# ppc_ddr2.net
KiCad netlist of a schematic drawn in Altium Designer
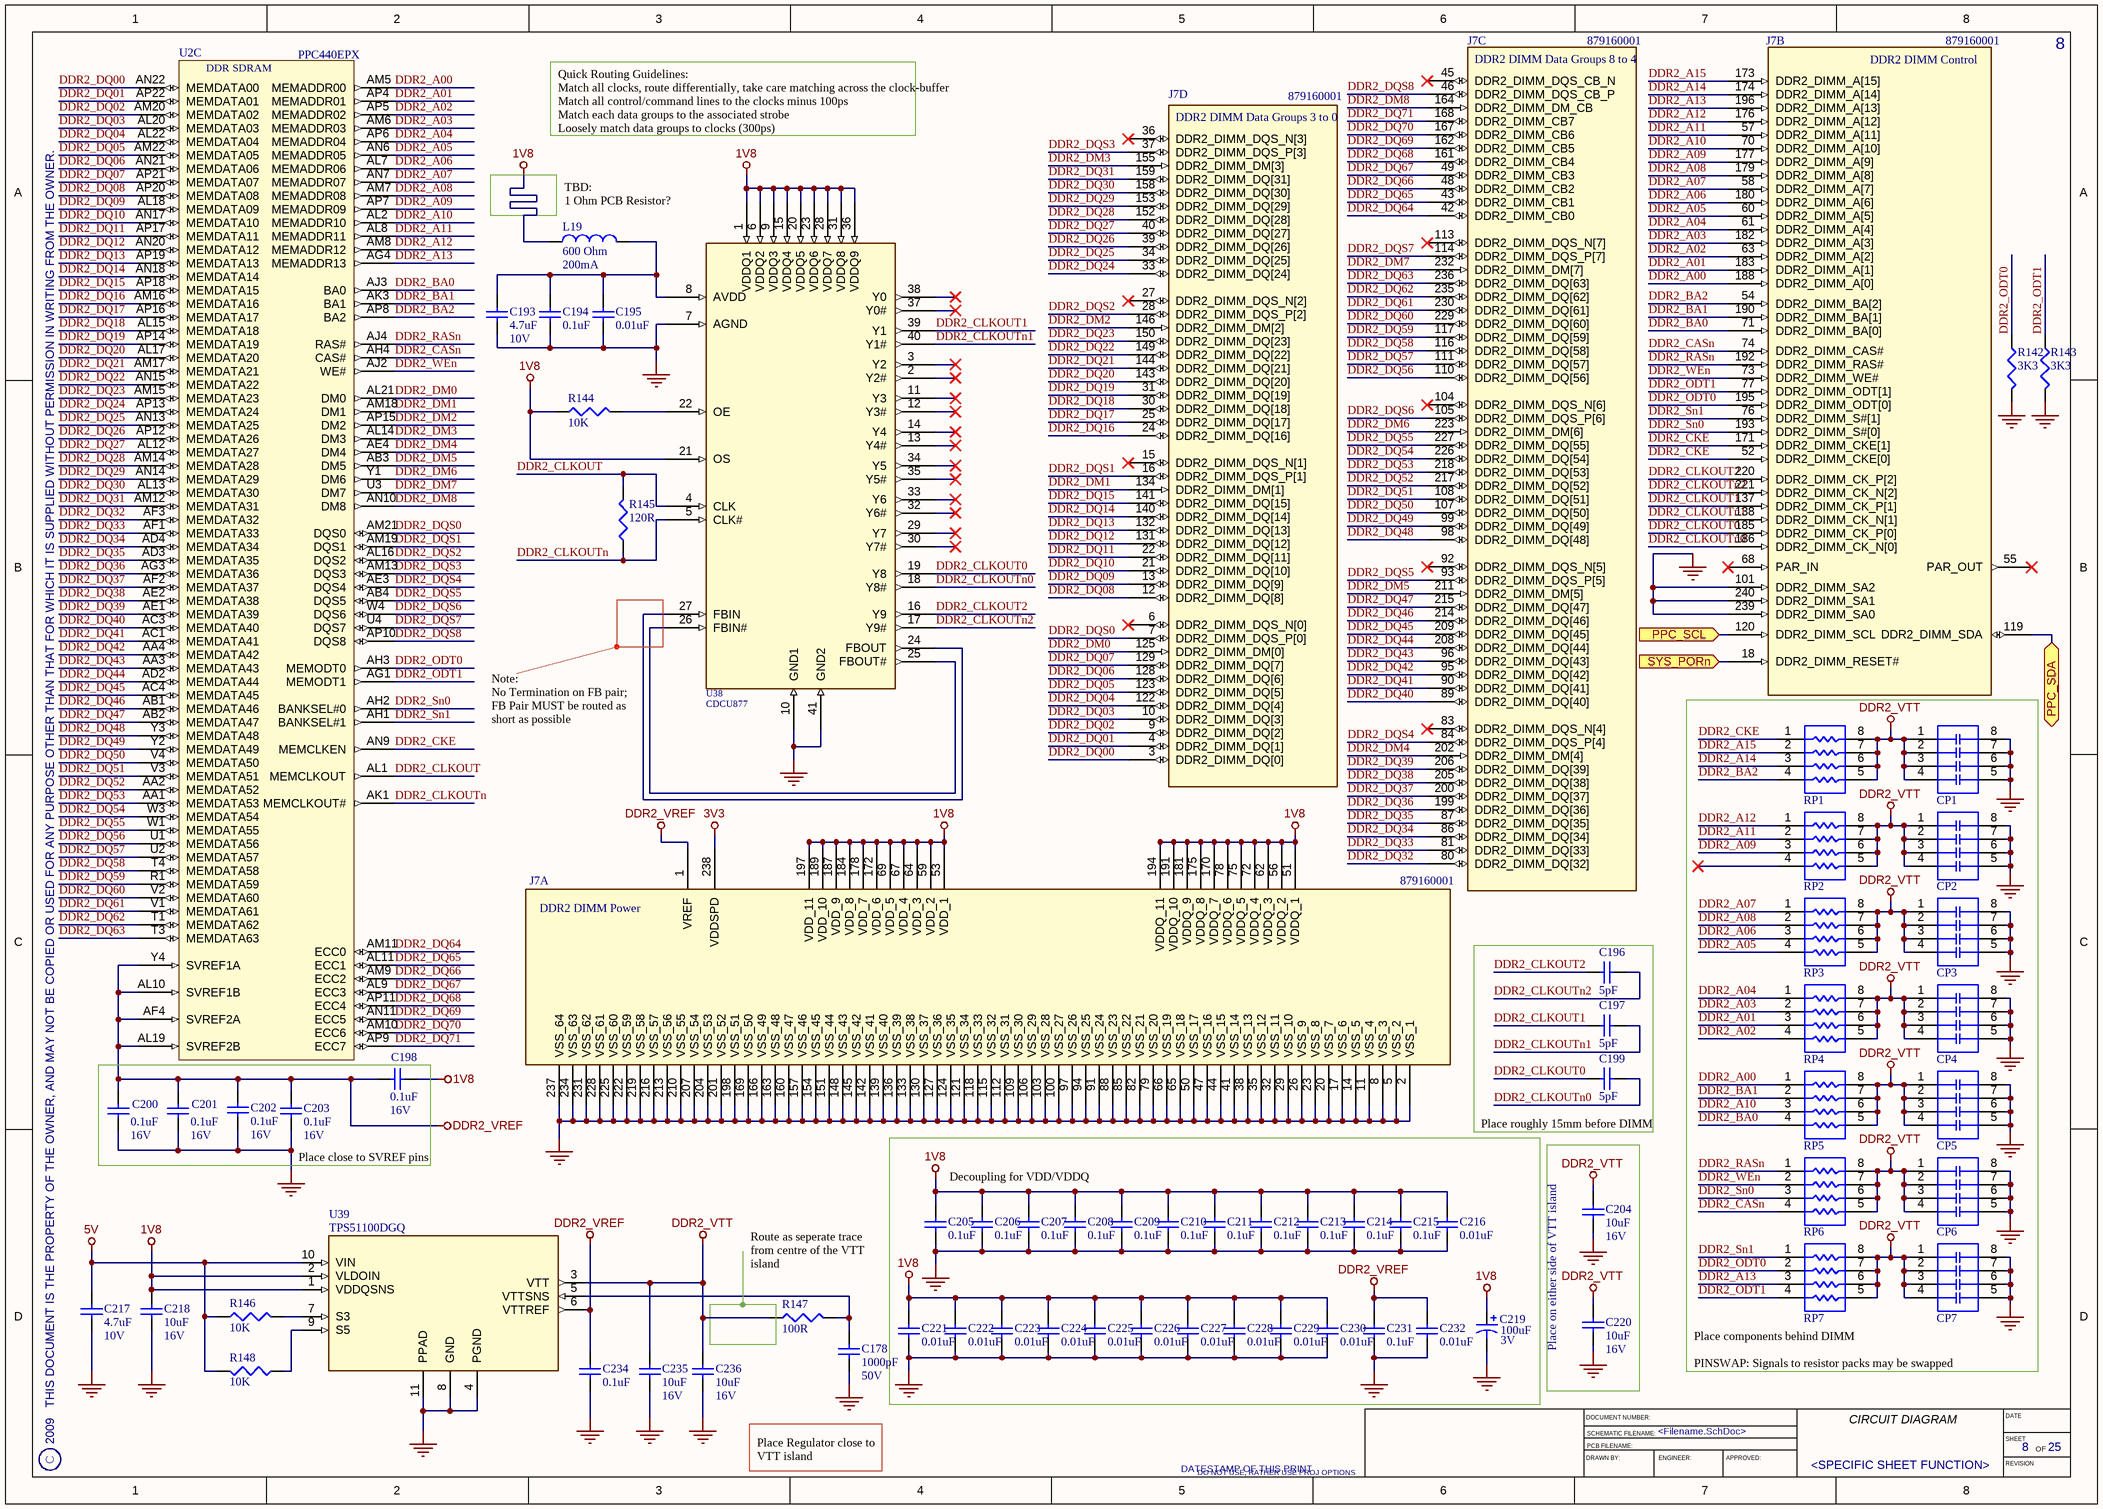
[diagram p0: ppc_ddr2.SchDoc]

(export (version "E")
  (design (tool "Eeschema 10.0.6"))
  (components
    (comp (ref "C178")
      (value "1000pF")
      (footprint "CAPC1005L")
      (description "Capacitor")
      (fields
        (field (name "MANUFACTURER") "Murata")
        (field (name "PART") "GRM155R61A102KA01B")
        (field (name "RATING") "50V")
      )
      (libsource (lib "SKA-MeerKAT_PASSIVE") (part "CapStd"))
    )
    (comp (ref "C193")
      (value "4.7uF")
      (footprint "2012-0805_CAPC2012X11N")
      (description "Capacitor")
      (fields
        (field (name "MANUFACTURER") "MURATA")
        (field (name "PART") "GRM21BR61E475KA12K")
        (field (name "RATING") "10V")
      )
      (libsource (lib "SKA-MeerKAT_PASSIVE") (part "CapStd"))
    )
    (comp (ref "C194")
      (value "0.1uF")
      (footprint "CAPC1005L")
      (description "Capacitor")
      (fields (field (name "MANUFACTURER") "MURATA") (field (name "PART") "GRM155R71A104KA01B"))
      (libsource (lib "SKA-MeerKAT_PASSIVE") (part "CapStd"))
    )
    (comp (ref "C195")
      (value "0.01uF")
      (footprint "CAPC1005L")
      (description "Capacitor")
      (fields (field (name "MANUFACTURER") "MURATA") (field (name "PART") "GRM155R7EA103KA01B"))
      (libsource (lib "SKA-MeerKAT_PASSIVE") (part "CapStd"))
    )
    (comp (ref "C196")
      (value "5pF")
      (footprint "CAPC1005L")
      (description "Capacitor")
      (fields (field (name "MANUFACTURER") "MURATA") (field (name "PART") "GRM1555C1H5R0CZ01B"))
      (libsource (lib "SKA-MeerKAT_PASSIVE") (part "CapStd"))
    )
    (comp (ref "C197")
      (value "5pF")
      (footprint "CAPC1005L")
      (description "Capacitor")
      (fields (field (name "MANUFACTURER") "MURATA") (field (name "PART") "GRM1555C1H5R0CZ01B"))
      (libsource (lib "SKA-MeerKAT_PASSIVE") (part "CapStd"))
    )
    (comp (ref "C198")
      (value "0.1uF")
      (footprint "CAPC1005L")
      (description "Capacitor")
      (fields
        (field (name "MANUFACTURER") "VENKEL")
        (field (name "PART") "C0402X7R160-104KN")
        (field (name "RATING") "16V")
      )
      (libsource (lib "SKA-MeerKAT_PASSIVE") (part "CapStd"))
    )
    (comp (ref "C199")
      (value "5pF")
      (footprint "CAPC1005L")
      (description "Capacitor")
      (fields (field (name "MANUFACTURER") "MURATA") (field (name "PART") "GRM1555C1H5R0CZ01B"))
      (libsource (lib "SKA-MeerKAT_PASSIVE") (part "CapStd"))
    )
    (comp (ref "C200")
      (value "0.1uF")
      (footprint "CAPC1005L")
      (description "Capacitor")
      (fields
        (field (name "MANUFACTURER") "VENKEL")
        (field (name "PART") "C0402X7R160-104KN")
        (field (name "RATING") "16V")
      )
      (libsource (lib "SKA-MeerKAT_PASSIVE") (part "CapStd"))
    )
    (comp (ref "C201")
      (value "0.1uF")
      (footprint "CAPC1005L")
      (description "Capacitor")
      (fields
        (field (name "MANUFACTURER") "VENKEL")
        (field (name "PART") "C0402X7R160-104KN")
        (field (name "RATING") "16V")
      )
      (libsource (lib "SKA-MeerKAT_PASSIVE") (part "CapStd"))
    )
    (comp (ref "C202")
      (value "0.1uF")
      (footprint "CAPC1005L")
      (description "Capacitor")
      (fields
        (field (name "MANUFACTURER") "VENKEL")
        (field (name "PART") "C0402X7R160-104KN")
        (field (name "RATING") "16V")
      )
      (libsource (lib "SKA-MeerKAT_PASSIVE") (part "CapStd"))
    )
    (comp (ref "C203")
      (value "0.1uF")
      (footprint "CAPC1005L")
      (description "Capacitor")
      (fields
        (field (name "MANUFACTURER") "VENKEL")
        (field (name "PART") "C0402X7R160-104KN")
        (field (name "RATING") "16V")
      )
      (libsource (lib "SKA-MeerKAT_PASSIVE") (part "CapStd"))
    )
    (comp (ref "C204")
      (value "10uF")
      (footprint "CAPC3225L")
      (description "Capacitor")
      (fields
        (field (name "MANUFACTURER") "MURATA")
        (field (name "PART") "GRM32DR61C106KA01K")
        (field (name "RATING") "16V")
      )
      (libsource (lib "SKA-MeerKAT_PASSIVE") (part "CapStd"))
    )
    (comp (ref "C205")
      (value "0.1uF")
      (footprint "CAPC1005L")
      (description "Capacitor")
      (fields (field (name "MANUFACTURER") "MURATA") (field (name "PART") "GRM155R71A104KA01B"))
      (libsource (lib "SKA-MeerKAT_PASSIVE") (part "CapStd"))
    )
    (comp (ref "C206")
      (value "0.1uF")
      (footprint "CAPC1005L")
      (description "Capacitor")
      (fields (field (name "MANUFACTURER") "MURATA") (field (name "PART") "GRM155R71A104KA01B"))
      (libsource (lib "SKA-MeerKAT_PASSIVE") (part "CapStd"))
    )
    (comp (ref "C207")
      (value "0.1uF")
      (footprint "CAPC1005L")
      (description "Capacitor")
      (fields (field (name "MANUFACTURER") "MURATA") (field (name "PART") "GRM155R71A104KA01B"))
      (libsource (lib "SKA-MeerKAT_PASSIVE") (part "CapStd"))
    )
    (comp (ref "C208")
      (value "0.1uF")
      (footprint "CAPC1005L")
      (description "Capacitor")
      (fields (field (name "MANUFACTURER") "MURATA") (field (name "PART") "GRM155R71A104KA01B"))
      (libsource (lib "SKA-MeerKAT_PASSIVE") (part "CapStd"))
    )
    (comp (ref "C209")
      (value "0.1uF")
      (footprint "CAPC1005L")
      (description "Capacitor")
      (fields (field (name "MANUFACTURER") "MURATA") (field (name "PART") "GRM155R71A104KA01B"))
      (libsource (lib "SKA-MeerKAT_PASSIVE") (part "CapStd"))
    )
    (comp (ref "C210")
      (value "0.1uF")
      (footprint "CAPC1005L")
      (description "Capacitor")
      (fields (field (name "MANUFACTURER") "MURATA") (field (name "PART") "GRM155R71A104KA01B"))
      (libsource (lib "SKA-MeerKAT_PASSIVE") (part "CapStd"))
    )
    (comp (ref "C211")
      (value "0.1uF")
      (footprint "CAPC1005L")
      (description "Capacitor")
      (fields (field (name "MANUFACTURER") "MURATA") (field (name "PART") "GRM155R71A104KA01B"))
      (libsource (lib "SKA-MeerKAT_PASSIVE") (part "CapStd"))
    )
    (comp (ref "C212")
      (value "0.1uF")
      (footprint "CAPC1005L")
      (description "Capacitor")
      (fields (field (name "MANUFACTURER") "MURATA") (field (name "PART") "GRM155R71A104KA01B"))
      (libsource (lib "SKA-MeerKAT_PASSIVE") (part "CapStd"))
    )
    (comp (ref "C213")
      (value "0.1uF")
      (footprint "CAPC1005L")
      (description "Capacitor")
      (fields (field (name "MANUFACTURER") "MURATA") (field (name "PART") "GRM155R71A104KA01B"))
      (libsource (lib "SKA-MeerKAT_PASSIVE") (part "CapStd"))
    )
    (comp (ref "C214")
      (value "0.1uF")
      (footprint "CAPC1005L")
      (description "Capacitor")
      (fields (field (name "MANUFACTURER") "MURATA") (field (name "PART") "GRM155R71A104KA01B"))
      (libsource (lib "SKA-MeerKAT_PASSIVE") (part "CapStd"))
    )
    (comp (ref "C215")
      (value "0.1uF")
      (footprint "CAPC1005L")
      (description "Capacitor")
      (fields (field (name "MANUFACTURER") "MURATA") (field (name "PART") "GRM155R71A104KA01B"))
      (libsource (lib "SKA-MeerKAT_PASSIVE") (part "CapStd"))
    )
    (comp (ref "C216")
      (value "0.01uF")
      (footprint "CAPC1005L")
      (description "Capacitor")
      (fields (field (name "MANUFACTURER") "MURATA") (field (name "PART") "GRM155R7EA103KA01B"))
      (libsource (lib "SKA-MeerKAT_PASSIVE") (part "CapStd"))
    )
    (comp (ref "C217")
      (value "4.7uF")
      (footprint "2012-0805_CAPC2012X11N")
      (description "Capacitor")
      (fields
        (field (name "MANUFACTURER") "MURATA")
        (field (name "PART") "GRM21BR61E475KA12K")
        (field (name "RATING") "10V")
      )
      (libsource (lib "SKA-MeerKAT_PASSIVE") (part "CapStd"))
    )
    (comp (ref "C218")
      (value "10uF")
      (footprint "CAPC3225L")
      (description "Capacitor")
      (fields
        (field (name "MANUFACTURER") "MURATA")
        (field (name "PART") "GRM32DR61C106KA01K")
        (field (name "RATING") "16V")
      )
      (libsource (lib "SKA-MeerKAT_PASSIVE") (part "CapStd"))
    )
    (comp (ref "C219")
      (value "100uF")
      (footprint "Tantalum-7343-CASE-D_CAPM7343X31N")
      (description "Polarized Capacitor")
      (fields
        (field (name "RATING") "3V")
        (field (name "MANUFACTURER") "AVX")
        (field (name "PART") "TPSB107K006R")
      )
      (libsource (lib "SKA-MeerKAT_PASSIVE") (part "CapPol"))
    )
    (comp (ref "C220")
      (value "10uF")
      (footprint "CAPC3225L")
      (description "Capacitor")
      (fields
        (field (name "MANUFACTURER") "MURATA")
        (field (name "PART") "GRM32DR61C106KA01K")
        (field (name "RATING") "16V")
      )
      (libsource (lib "SKA-MeerKAT_PASSIVE") (part "CapStd"))
    )
    (comp (ref "C221")
      (value "0.01uF")
      (footprint "CAPC1005L")
      (description "Capacitor")
      (fields (field (name "MANUFACTURER") "MURATA") (field (name "PART") "GRM155R7EA103KA01B"))
      (libsource (lib "SKA-MeerKAT_PASSIVE") (part "CapStd"))
    )
    (comp (ref "C222")
      (value "0.01uF")
      (footprint "CAPC1005L")
      (description "Capacitor")
      (fields (field (name "MANUFACTURER") "MURATA") (field (name "PART") "GRM155R7EA103KA01B"))
      (libsource (lib "SKA-MeerKAT_PASSIVE") (part "CapStd"))
    )
    (comp (ref "C223")
      (value "0.01uF")
      (footprint "CAPC1005L")
      (description "Capacitor")
      (fields (field (name "MANUFACTURER") "MURATA") (field (name "PART") "GRM155R7EA103KA01B"))
      (libsource (lib "SKA-MeerKAT_PASSIVE") (part "CapStd"))
    )
    (comp (ref "C224")
      (value "0.01uF")
      (footprint "CAPC1005L")
      (description "Capacitor")
      (fields (field (name "MANUFACTURER") "MURATA") (field (name "PART") "GRM155R7EA103KA01B"))
      (libsource (lib "SKA-MeerKAT_PASSIVE") (part "CapStd"))
    )
    (comp (ref "C225")
      (value "0.01uF")
      (footprint "CAPC1005L")
      (description "Capacitor")
      (fields (field (name "MANUFACTURER") "MURATA") (field (name "PART") "GRM155R7EA103KA01B"))
      (libsource (lib "SKA-MeerKAT_PASSIVE") (part "CapStd"))
    )
    (comp (ref "C226")
      (value "0.01uF")
      (footprint "CAPC1005L")
      (description "Capacitor")
      (fields (field (name "MANUFACTURER") "MURATA") (field (name "PART") "GRM155R7EA103KA01B"))
      (libsource (lib "SKA-MeerKAT_PASSIVE") (part "CapStd"))
    )
    (comp (ref "C227")
      (value "0.01uF")
      (footprint "CAPC1005L")
      (description "Capacitor")
      (fields (field (name "MANUFACTURER") "MURATA") (field (name "PART") "GRM155R7EA103KA01B"))
      (libsource (lib "SKA-MeerKAT_PASSIVE") (part "CapStd"))
    )
    (comp (ref "C228")
      (value "0.01uF")
      (footprint "CAPC1005L")
      (description "Capacitor")
      (fields (field (name "MANUFACTURER") "MURATA") (field (name "PART") "GRM155R7EA103KA01B"))
      (libsource (lib "SKA-MeerKAT_PASSIVE") (part "CapStd"))
    )
    (comp (ref "C229")
      (value "0.01uF")
      (footprint "CAPC1005L")
      (description "Capacitor")
      (fields (field (name "MANUFACTURER") "MURATA") (field (name "PART") "GRM155R7EA103KA01B"))
      (libsource (lib "SKA-MeerKAT_PASSIVE") (part "CapStd"))
    )
    (comp (ref "C230")
      (value "0.01uF")
      (footprint "CAPC1005L")
      (description "Capacitor")
      (fields (field (name "MANUFACTURER") "MURATA") (field (name "PART") "GRM155R7EA103KA01B"))
      (libsource (lib "SKA-MeerKAT_PASSIVE") (part "CapStd"))
    )
    (comp (ref "C231")
      (value "0.1uF")
      (footprint "CAPC1005L")
      (description "Capacitor")
      (fields (field (name "MANUFACTURER") "MURATA") (field (name "PART") "GRM155R71A104KA01B"))
      (libsource (lib "SKA-MeerKAT_PASSIVE") (part "CapStd"))
    )
    (comp (ref "C232")
      (value "0.01uF")
      (footprint "CAPC1005L")
      (description "Capacitor")
      (fields (field (name "MANUFACTURER") "MURATA") (field (name "PART") "GRM155R7EA103KA01B"))
      (libsource (lib "SKA-MeerKAT_PASSIVE") (part "CapStd"))
    )
    (comp (ref "C234")
      (value "0.1uF")
      (footprint "CAPC1005L")
      (description "Capacitor")
      (fields (field (name "MANUFACTURER") "MURATA") (field (name "PART") "GRM155R71A104KA01B"))
      (libsource (lib "SKA-MeerKAT_PASSIVE") (part "CapStd"))
    )
    (comp (ref "C235")
      (value "10uF")
      (footprint "CAPC3225L")
      (description "Capacitor")
      (fields
        (field (name "MANUFACTURER") "MURATA")
        (field (name "PART") "GRM32DR61C106KA01K")
        (field (name "RATING") "16V")
      )
      (libsource (lib "SKA-MeerKAT_PASSIVE") (part "CapStd"))
    )
    (comp (ref "C236")
      (value "10uF")
      (footprint "CAPC3225L")
      (description "Capacitor")
      (fields
        (field (name "MANUFACTURER") "MURATA")
        (field (name "PART") "GRM32DR61C106KA01K")
        (field (name "RATING") "16V")
      )
      (libsource (lib "SKA-MeerKAT_PASSIVE") (part "CapStd"))
    )
    (comp (ref "CP1")
      (value "CapPack4")
      (footprint "CAPCAF50P125X200X100-8N")
      (description "Isolated Capacitor Network")
      (fields (field (name "PART") "GNM214B11C104MA01B") (field (name "MANUFACTURER") "MURATA"))
      (libsource (lib "SKA-MeerKAT_PASSIVE") (part "CapPack4"))
    )
    (comp (ref "CP2")
      (value "CapPack4")
      (footprint "CAPCAF50P125X200X100-8N")
      (description "Isolated Capacitor Network")
      (fields (field (name "PART") "GNM214B11C104MA01B") (field (name "MANUFACTURER") "MURATA"))
      (libsource (lib "SKA-MeerKAT_PASSIVE") (part "CapPack4"))
    )
    (comp (ref "CP3")
      (value "CapPack4")
      (footprint "CAPCAF50P125X200X100-8N")
      (description "Isolated Capacitor Network")
      (fields (field (name "PART") "GNM214B11C104MA01B") (field (name "MANUFACTURER") "MURATA"))
      (libsource (lib "SKA-MeerKAT_PASSIVE") (part "CapPack4"))
    )
    (comp (ref "CP4")
      (value "CapPack4")
      (footprint "CAPCAF50P125X200X100-8N")
      (description "Isolated Capacitor Network")
      (fields (field (name "PART") "GNM214B11C104MA01B") (field (name "MANUFACTURER") "MURATA"))
      (libsource (lib "SKA-MeerKAT_PASSIVE") (part "CapPack4"))
    )
    (comp (ref "CP5")
      (value "CapPack4")
      (footprint "CAPCAF50P125X200X100-8N")
      (description "Isolated Capacitor Network")
      (fields (field (name "PART") "GNM214B11C104MA01B") (field (name "MANUFACTURER") "MURATA"))
      (libsource (lib "SKA-MeerKAT_PASSIVE") (part "CapPack4"))
    )
    (comp (ref "CP6")
      (value "CapPack4")
      (footprint "CAPCAF50P125X200X100-8N")
      (description "Isolated Capacitor Network")
      (fields (field (name "PART") "GNM214B11C104MA01B") (field (name "MANUFACTURER") "MURATA"))
      (libsource (lib "SKA-MeerKAT_PASSIVE") (part "CapPack4"))
    )
    (comp (ref "CP7")
      (value "CapPack4")
      (footprint "CAPCAF50P125X200X100-8N")
      (description "Isolated Capacitor Network")
      (fields (field (name "PART") "GNM214B11C104MA01B") (field (name "MANUFACTURER") "MURATA"))
      (libsource (lib "SKA-MeerKAT_PASSIVE") (part "CapPack4"))
    )
    (comp (ref "J7")
      (value "879160001")
      (footprint "MOLEX87916001")
      (description "240-pin DDR2 DIMM Socket")
      (fields (field (name "MANUFACTURER") "MOLEX"))
      (libsource (lib "SKA-MeerKAT_CONNECTOR") (part "ddr2_dimm_240"))
    )
    (comp (ref "L19")
      (value "600 Ohm")
      (footprint "INDC2012L")
      (description "Inductor")
      (fields
        (field (name "MANUFACTURER") "Murata")
        (field (name "PART") "BLM21B601SPT")
        (field (name "RATING") "200mA")
      )
      (libsource (lib "SKA-MeerKAT_PASSIVE") (part "Inductor"))
    )
    (comp (ref "R142")
      (value "3K3")
      (footprint "RESC1608L")
      (description "Resistor")
      (fields (field (name "PART") "0402WGJ033T1E") (field (name "MANUFACTURER") "ROYALOHM"))
      (libsource (lib "SKA-MeerKAT_PASSIVE") (part "ResStd"))
    )
    (comp (ref "R143")
      (value "3K3")
      (footprint "RESC1608L")
      (description "Resistor")
      (fields (field (name "PART") "0402WGJ033T1E") (field (name "MANUFACTURER") "ROYALOHM"))
      (libsource (lib "SKA-MeerKAT_PASSIVE") (part "ResStd"))
    )
    (comp (ref "R144")
      (value "10K")
      (footprint "RESC1608L")
      (description "Resistor")
      (fields (field (name "PART") "0402WGJ103T1E") (field (name "MANUFACTURER") "ROYALOHM"))
      (libsource (lib "SKA-MeerKAT_PASSIVE") (part "ResStd"))
    )
    (comp (ref "R145")
      (value "120R")
      (footprint "RESC1005L")
      (description "Resistor")
      (fields (field (name "PART") "0402WGJ0120T1E") (field (name "MANUFACTURER") "ROYALOHM"))
      (libsource (lib "SKA-MeerKAT_PASSIVE") (part "ResStd"))
    )
    (comp (ref "R146")
      (value "10K")
      (footprint "RESC1005L")
      (description "Resistor")
      (fields (field (name "PART") "0402WGJ103T1E") (field (name "MANUFACTURER") "ROYALOHM"))
      (libsource (lib "SKA-MeerKAT_PASSIVE") (part "ResStd"))
    )
    (comp (ref "R147")
      (value "100R")
      (footprint "RESC1005L")
      (description "Resistor")
      (fields (field (name "PART") "0402WGJ0101T1E") (field (name "MANUFACTURER") "ROYALOHM"))
      (libsource (lib "SKA-MeerKAT_PASSIVE") (part "ResStd"))
    )
    (comp (ref "R148")
      (value "10K")
      (footprint "RESC1005L")
      (description "Resistor")
      (fields (field (name "PART") "0402WGJ103T1E") (field (name "MANUFACTURER") "ROYALOHM"))
      (libsource (lib "SKA-MeerKAT_PASSIVE") (part "ResStd"))
    )
    (comp (ref "RP1")
      (value "ResPack4")
      (footprint "RESCAV50P100X200X55-8N")
      (description "Isolated Resistor Network")
      (fields (field (name "PART") "4D02WGJ0510B1E") (field (name "MANUFACTURER") "ROYAL OHM"))
      (libsource (lib "SKA-MeerKAT_PASSIVE") (part "ResPack4"))
    )
    (comp (ref "RP2")
      (value "ResPack4")
      (footprint "RESCAV50P100X200X55-8N")
      (description "Isolated Resistor Network")
      (fields (field (name "PART") "4D02WGJ0510B1E") (field (name "MANUFACTURER") "ROYAL OHM"))
      (libsource (lib "SKA-MeerKAT_PASSIVE") (part "ResPack4"))
    )
    (comp (ref "RP3")
      (value "ResPack4")
      (footprint "RESCAV50P100X200X55-8N")
      (description "Isolated Resistor Network")
      (fields (field (name "PART") "4D02WGJ0510B1E") (field (name "MANUFACTURER") "ROYAL OHM"))
      (libsource (lib "SKA-MeerKAT_PASSIVE") (part "ResPack4"))
    )
    (comp (ref "RP4")
      (value "ResPack4")
      (footprint "RESCAV50P100X200X55-8N")
      (description "Isolated Resistor Network")
      (fields (field (name "PART") "4D02WGJ0510B1E") (field (name "MANUFACTURER") "ROYAL OHM"))
      (libsource (lib "SKA-MeerKAT_PASSIVE") (part "ResPack4"))
    )
    (comp (ref "RP5")
      (value "ResPack4")
      (footprint "RESCAV50P100X200X55-8N")
      (description "Isolated Resistor Network")
      (fields (field (name "PART") "4D02WGJ0510B1E") (field (name "MANUFACTURER") "ROYAL OHM"))
      (libsource (lib "SKA-MeerKAT_PASSIVE") (part "ResPack4"))
    )
    (comp (ref "RP6")
      (value "ResPack4")
      (footprint "RESCAV50P100X200X55-8N")
      (description "Isolated Resistor Network")
      (fields (field (name "PART") "4D02WGJ0510B1E") (field (name "MANUFACTURER") "ROYAL OHM"))
      (libsource (lib "SKA-MeerKAT_PASSIVE") (part "ResPack4"))
    )
    (comp (ref "RP7")
      (value "ResPack4")
      (footprint "RESCAV50P100X200X55-8N")
      (description "Isolated Resistor Network")
      (fields (field (name "PART") "4D02WGJ0510B1E") (field (name "MANUFACTURER") "ROYAL OHM"))
      (libsource (lib "SKA-MeerKAT_PASSIVE") (part "ResPack4"))
    )
    (comp (ref "U2")
      (value "PPC440EPX")
      (footprint "BGA680C100P34X34_3500X3500X265")
      (description "Applied Micro PPC440EPx")
      (fields (field (name "PART") "PPC440EPX-NTA533T") (field (name "MANUFACTURER") "AMCC"))
      (libsource (lib "SKA-MeerKAT_IC") (part "PPC440EPX"))
    )
    (comp (ref "U38")
      (value "CDCU877")
      (footprint "PQFN50P602X602X100-41N")
      (description "SSTL Zero-Delay Clock Buffer")
      (fields (field (name "MANUFACTURER") "Texas Instruments"))
      (libsource (lib "SKA-MeerKAT_IC") (part "CDCU877"))
    )
    (comp (ref "U39")
      (value "TPS51100DGQ")
      (footprint "SOP50P490X110-11N")
      (description "3A Sink/Source Regulator")
      (fields (field (name "MANUFACTURER") "Texas Instruments"))
      (libsource (lib "SKA-MeerKAT_IC") (part "TPS51100DGQ"))
    )
  )
  (nets
    (net (code "1") (name "/DDR2_A00") (class "Default")
      (node (ref "J7") (pin "188") (pinfunction "DDR2_DIMM_A[0]_188") (pintype "input"))
      (node (ref "RP5") (pin "1") (pinfunction "1_1") (pintype "passive"))
      (node (ref "U2") (pin "AM5") (pinfunction "MEMADDR00_AM5") (pintype "output"))
    )
    (net (code "2") (name "/DDR2_A01") (class "Default")
      (node (ref "J7") (pin "183") (pinfunction "DDR2_DIMM_A[1]_183") (pintype "input"))
      (node (ref "RP4") (pin "3") (pinfunction "3_3") (pintype "passive"))
      (node (ref "U2") (pin "AP4") (pinfunction "MEMADDR01_AP4") (pintype "output"))
    )
    (net (code "3") (name "/DDR2_A02") (class "Default")
      (node (ref "J7") (pin "63") (pinfunction "DDR2_DIMM_A[2]_63") (pintype "input"))
      (node (ref "RP4") (pin "4") (pinfunction "4_4") (pintype "passive"))
      (node (ref "U2") (pin "AP5") (pinfunction "MEMADDR02_AP5") (pintype "output"))
    )
    (net (code "4") (name "/DDR2_A03") (class "Default")
      (node (ref "J7") (pin "182") (pinfunction "DDR2_DIMM_A[3]_182") (pintype "input"))
      (node (ref "RP4") (pin "2") (pinfunction "2_2") (pintype "passive"))
      (node (ref "U2") (pin "AM6") (pinfunction "MEMADDR03_AM6") (pintype "output"))
    )
    (net (code "5") (name "/DDR2_A04") (class "Default")
      (node (ref "J7") (pin "61") (pinfunction "DDR2_DIMM_A[4]_61") (pintype "input"))
      (node (ref "RP4") (pin "1") (pinfunction "1_1") (pintype "passive"))
      (node (ref "U2") (pin "AP6") (pinfunction "MEMADDR04_AP6") (pintype "output"))
    )
    (net (code "6") (name "/DDR2_A05") (class "Default")
      (node (ref "J7") (pin "60") (pinfunction "DDR2_DIMM_A[5]_60") (pintype "input"))
      (node (ref "RP3") (pin "4") (pinfunction "4_4") (pintype "passive"))
      (node (ref "U2") (pin "AN6") (pinfunction "MEMADDR05_AN6") (pintype "output"))
    )
    (net (code "7") (name "/DDR2_A06") (class "Default")
      (node (ref "J7") (pin "180") (pinfunction "DDR2_DIMM_A[6]_180") (pintype "input"))
      (node (ref "RP3") (pin "3") (pinfunction "3_3") (pintype "passive"))
      (node (ref "U2") (pin "AL7") (pinfunction "MEMADDR06_AL7") (pintype "output"))
    )
    (net (code "8") (name "/DDR2_A07") (class "Default")
      (node (ref "J7") (pin "58") (pinfunction "DDR2_DIMM_A[7]_58") (pintype "input"))
      (node (ref "RP3") (pin "1") (pinfunction "1_1") (pintype "passive"))
      (node (ref "U2") (pin "AN7") (pinfunction "MEMADDR07_AN7") (pintype "output"))
    )
    (net (code "9") (name "/DDR2_A08") (class "Default")
      (node (ref "J7") (pin "179") (pinfunction "DDR2_DIMM_A[8]_179") (pintype "input"))
      (node (ref "RP3") (pin "2") (pinfunction "2_2") (pintype "passive"))
      (node (ref "U2") (pin "AM7") (pinfunction "MEMADDR08_AM7") (pintype "output"))
    )
    (net (code "10") (name "/DDR2_A09") (class "Default")
      (node (ref "J7") (pin "177") (pinfunction "DDR2_DIMM_A[9]_177") (pintype "input"))
      (node (ref "RP2") (pin "3") (pinfunction "3_3") (pintype "passive"))
      (node (ref "U2") (pin "AP7") (pinfunction "MEMADDR09_AP7") (pintype "output"))
    )
    (net (code "11") (name "/DDR2_A10") (class "Default")
      (node (ref "J7") (pin "70") (pinfunction "DDR2_DIMM_A[10]_70") (pintype "input"))
      (node (ref "RP5") (pin "3") (pinfunction "3_3") (pintype "passive"))
      (node (ref "U2") (pin "AL2") (pinfunction "MEMADDR10_AL2") (pintype "output"))
    )
    (net (code "12") (name "/DDR2_A11") (class "Default")
      (node (ref "J7") (pin "57") (pinfunction "DDR2_DIMM_A[11]_57") (pintype "input"))
      (node (ref "RP2") (pin "2") (pinfunction "2_2") (pintype "passive"))
      (node (ref "U2") (pin "AL8") (pinfunction "MEMADDR11_AL8") (pintype "output"))
    )
    (net (code "13") (name "/DDR2_A12") (class "Default")
      (node (ref "J7") (pin "176") (pinfunction "DDR2_DIMM_A[12]_176") (pintype "input"))
      (node (ref "RP2") (pin "1") (pinfunction "1_1") (pintype "passive"))
      (node (ref "U2") (pin "AM8") (pinfunction "MEMADDR12_AM8") (pintype "output"))
    )
    (net (code "14") (name "/DDR2_A13") (class "Default")
      (node (ref "J7") (pin "196") (pinfunction "DDR2_DIMM_A[13]_196") (pintype "input"))
      (node (ref "RP7") (pin "3") (pinfunction "3_3") (pintype "passive"))
      (node (ref "U2") (pin "AG4") (pinfunction "MEMADDR13_AG4") (pintype "output"))
    )
    (net (code "15") (name "/DDR2_A14") (class "Default")
      (node (ref "J7") (pin "174") (pinfunction "DDR2_DIMM_A[14]_174") (pintype "input"))
      (node (ref "RP1") (pin "3") (pinfunction "3_3") (pintype "passive"))
    )
    (net (code "16") (name "/DDR2_A15") (class "Default")
      (node (ref "J7") (pin "173") (pinfunction "DDR2_DIMM_A[15]_173") (pintype "input"))
      (node (ref "RP1") (pin "2") (pinfunction "2_2") (pintype "passive"))
    )
    (net (code "17") (name "/DDR2_BA0") (class "Default")
      (node (ref "J7") (pin "71") (pinfunction "DDR2_DIMM_BA[0]_71") (pintype "input"))
      (node (ref "RP5") (pin "4") (pinfunction "4_4") (pintype "passive"))
      (node (ref "U2") (pin "AJ3") (pinfunction "BA0_AJ3") (pintype "output"))
    )
    (net (code "18") (name "/DDR2_BA1") (class "Default")
      (node (ref "J7") (pin "190") (pinfunction "DDR2_DIMM_BA[1]_190") (pintype "input"))
      (node (ref "RP5") (pin "2") (pinfunction "2_2") (pintype "passive"))
      (node (ref "U2") (pin "AK3") (pinfunction "BA1_AK3") (pintype "output"))
    )
    (net (code "19") (name "/DDR2_BA2") (class "Default")
      (node (ref "J7") (pin "54") (pinfunction "DDR2_DIMM_BA[2]_54") (pintype "input"))
      (node (ref "RP1") (pin "4") (pinfunction "4_4") (pintype "passive"))
      (node (ref "U2") (pin "AP8") (pinfunction "BA2_AP8") (pintype "output"))
    )
    (net (code "20") (name "/DDR2_CASn") (class "Default")
      (node (ref "J7") (pin "74") (pinfunction "DDR2_DIMM_CAS#_74") (pintype "input"))
      (node (ref "RP6") (pin "4") (pinfunction "4_4") (pintype "passive"))
      (node (ref "U2") (pin "AH4") (pinfunction "CAS#_AH4") (pintype "output"))
    )
    (net (code "21") (name "/DDR2_CKE") (class "Default")
      (node (ref "J7") (pin "171") (pinfunction "DDR2_DIMM_CKE[1]_171") (pintype "input"))
      (node (ref "J7") (pin "52") (pinfunction "DDR2_DIMM_CKE[0]_52") (pintype "input"))
      (node (ref "RP1") (pin "1") (pinfunction "1_1") (pintype "passive"))
      (node (ref "U2") (pin "AN9") (pinfunction "MEMCLKEN_AN9") (pintype "output"))
    )
    (net (code "22") (name "/DDR2_CLKOUT") (class "Default")
      (node (ref "R145") (pin "2") (pinfunction "2_2") (pintype "passive"))
      (node (ref "U2") (pin "AL1") (pinfunction "MEMCLKOUT_AL1") (pintype "output"))
      (node (ref "U38") (pin "4") (pinfunction "CLK_4") (pintype "input"))
    )
    (net (code "23") (name "/DDR2_CLKOUT0") (class "Default")
      (node (ref "C199") (pin "1") (pinfunction "1_1") (pintype "passive"))
      (node (ref "J7") (pin "185") (pinfunction "DDR2_DIMM_CK_P[0]_185") (pintype "input"))
      (node (ref "U38") (pin "19") (pinfunction "Y8_19") (pintype "output"))
    )
    (net (code "24") (name "/DDR2_CLKOUT1") (class "Default")
      (node (ref "C197") (pin "1") (pinfunction "1_1") (pintype "passive"))
      (node (ref "J7") (pin "137") (pinfunction "DDR2_DIMM_CK_P[1]_137") (pintype "input"))
      (node (ref "U38") (pin "39") (pinfunction "Y1_39") (pintype "output"))
    )
    (net (code "25") (name "/DDR2_CLKOUT2") (class "Default")
      (node (ref "C196") (pin "1") (pinfunction "1_1") (pintype "passive"))
      (node (ref "J7") (pin "220") (pinfunction "DDR2_DIMM_CK_P[2]_220") (pintype "input"))
      (node (ref "U38") (pin "16") (pinfunction "Y9_16") (pintype "output"))
    )
    (net (code "26") (name "/DDR2_CLKOUTn") (class "Default")
      (node (ref "R145") (pin "1") (pinfunction "1_1") (pintype "passive"))
      (node (ref "U2") (pin "AK1") (pinfunction "MEMCLKOUT#_AK1") (pintype "output"))
      (node (ref "U38") (pin "5") (pinfunction "CLK#_5") (pintype "input"))
    )
    (net (code "27") (name "/DDR2_CLKOUTn0") (class "Default")
      (node (ref "C199") (pin "2") (pinfunction "2_2") (pintype "passive"))
      (node (ref "J7") (pin "186") (pinfunction "DDR2_DIMM_CK_N[0]_186") (pintype "input"))
      (node (ref "U38") (pin "18") (pinfunction "Y8#_18") (pintype "output"))
    )
    (net (code "28") (name "/DDR2_CLKOUTn1") (class "Default")
      (node (ref "C197") (pin "2") (pinfunction "2_2") (pintype "passive"))
      (node (ref "J7") (pin "138") (pinfunction "DDR2_DIMM_CK_N[1]_138") (pintype "input"))
      (node (ref "U38") (pin "40") (pinfunction "Y1#_40") (pintype "output"))
    )
    (net (code "29") (name "/DDR2_CLKOUTn2") (class "Default")
      (node (ref "C196") (pin "2") (pinfunction "2_2") (pintype "passive"))
      (node (ref "J7") (pin "221") (pinfunction "DDR2_DIMM_CK_N[2]_221") (pintype "input"))
      (node (ref "U38") (pin "17") (pinfunction "Y9#_17") (pintype "output"))
    )
    (net (code "30") (name "/DDR2_DM0") (class "Default")
      (node (ref "J7") (pin "125") (pinfunction "DDR2_DIMM_DM[0]_125") (pintype "input"))
      (node (ref "U2") (pin "AL21") (pinfunction "DM0_AL21") (pintype "output"))
    )
    (net (code "31") (name "/DDR2_DM1") (class "Default")
      (node (ref "J7") (pin "134") (pinfunction "DDR2_DIMM_DM[1]_134") (pintype "input"))
      (node (ref "U2") (pin "AM18") (pinfunction "DM1_AM18") (pintype "output"))
    )
    (net (code "32") (name "/DDR2_DM2") (class "Default")
      (node (ref "J7") (pin "146") (pinfunction "DDR2_DIMM_DM[2]_146") (pintype "input"))
      (node (ref "U2") (pin "AP15") (pinfunction "DM2_AP15") (pintype "output"))
    )
    (net (code "33") (name "/DDR2_DM3") (class "Default")
      (node (ref "J7") (pin "155") (pinfunction "DDR2_DIMM_DM[3]_155") (pintype "input"))
      (node (ref "U2") (pin "AL14") (pinfunction "DM3_AL14") (pintype "output"))
    )
    (net (code "34") (name "/DDR2_DM4") (class "Default")
      (node (ref "J7") (pin "202") (pinfunction "DDR2_DIMM_DM[4]_202") (pintype "input"))
      (node (ref "U2") (pin "AE4") (pinfunction "DM4_AE4") (pintype "output"))
    )
    (net (code "35") (name "/DDR2_DM5") (class "Default")
      (node (ref "J7") (pin "211") (pinfunction "DDR2_DIMM_DM[5]_211") (pintype "input"))
      (node (ref "U2") (pin "AB3") (pinfunction "DM5_AB3") (pintype "output"))
    )
    (net (code "36") (name "/DDR2_DM6") (class "Default")
      (node (ref "J7") (pin "223") (pinfunction "DDR2_DIMM_DM[6]_223") (pintype "input"))
      (node (ref "U2") (pin "Y1") (pinfunction "DM6_Y1") (pintype "output"))
    )
    (net (code "37") (name "/DDR2_DM7") (class "Default")
      (node (ref "J7") (pin "232") (pinfunction "DDR2_DIMM_DM[7]_232") (pintype "input"))
      (node (ref "U2") (pin "U3") (pinfunction "DM7_U3") (pintype "output"))
    )
    (net (code "38") (name "/DDR2_DM8") (class "Default")
      (node (ref "J7") (pin "164") (pinfunction "DDR2_DIMM_DM_CB_164") (pintype "input"))
      (node (ref "U2") (pin "AN10") (pinfunction "DM8_AN10") (pintype "output"))
    )
    (net (code "39") (name "/DDR2_DQ00") (class "Default")
      (node (ref "J7") (pin "3") (pinfunction "DDR2_DIMM_DQ[0]_3") (pintype "bidirectional"))
      (node (ref "U2") (pin "AN22") (pinfunction "MEMDATA00_AN22") (pintype "bidirectional"))
    )
    (net (code "40") (name "/DDR2_DQ01") (class "Default")
      (node (ref "J7") (pin "4") (pinfunction "DDR2_DIMM_DQ[1]_4") (pintype "bidirectional"))
      (node (ref "U2") (pin "AP22") (pinfunction "MEMDATA01_AP22") (pintype "bidirectional"))
    )
    (net (code "41") (name "/DDR2_DQ02") (class "Default")
      (node (ref "J7") (pin "9") (pinfunction "DDR2_DIMM_DQ[2]_9") (pintype "bidirectional"))
      (node (ref "U2") (pin "AM20") (pinfunction "MEMDATA02_AM20") (pintype "bidirectional"))
    )
    (net (code "42") (name "/DDR2_DQ03") (class "Default")
      (node (ref "J7") (pin "10") (pinfunction "DDR2_DIMM_DQ[3]_10") (pintype "bidirectional"))
      (node (ref "U2") (pin "AL20") (pinfunction "MEMDATA03_AL20") (pintype "bidirectional"))
    )
    (net (code "43") (name "/DDR2_DQ04") (class "Default")
      (node (ref "J7") (pin "122") (pinfunction "DDR2_DIMM_DQ[4]_122") (pintype "bidirectional"))
      (node (ref "U2") (pin "AL22") (pinfunction "MEMDATA04_AL22") (pintype "bidirectional"))
    )
    (net (code "44") (name "/DDR2_DQ05") (class "Default")
      (node (ref "J7") (pin "123") (pinfunction "DDR2_DIMM_DQ[5]_123") (pintype "bidirectional"))
      (node (ref "U2") (pin "AM22") (pinfunction "MEMDATA05_AM22") (pintype "bidirectional"))
    )
    (net (code "45") (name "/DDR2_DQ06") (class "Default")
      (node (ref "J7") (pin "128") (pinfunction "DDR2_DIMM_DQ[6]_128") (pintype "bidirectional"))
      (node (ref "U2") (pin "AN21") (pinfunction "MEMDATA06_AN21") (pintype "bidirectional"))
    )
    (net (code "46") (name "/DDR2_DQ07") (class "Default")
      (node (ref "J7") (pin "129") (pinfunction "DDR2_DIMM_DQ[7]_129") (pintype "bidirectional"))
      (node (ref "U2") (pin "AP21") (pinfunction "MEMDATA07_AP21") (pintype "bidirectional"))
    )
    (net (code "47") (name "/DDR2_DQ08") (class "Default")
      (node (ref "J7") (pin "12") (pinfunction "DDR2_DIMM_DQ[8]_12") (pintype "bidirectional"))
      (node (ref "U2") (pin "AP20") (pinfunction "MEMDATA08_AP20") (pintype "bidirectional"))
    )
    (net (code "48") (name "/DDR2_DQ09") (class "Default")
      (node (ref "J7") (pin "13") (pinfunction "DDR2_DIMM_DQ[9]_13") (pintype "bidirectional"))
      (node (ref "U2") (pin "AL18") (pinfunction "MEMDATA09_AL18") (pintype "bidirectional"))
    )
    (net (code "49") (name "/DDR2_DQ10") (class "Default")
      (node (ref "J7") (pin "21") (pinfunction "DDR2_DIMM_DQ[10]_21") (pintype "bidirectional"))
      (node (ref "U2") (pin "AN17") (pinfunction "MEMDATA10_AN17") (pintype "bidirectional"))
    )
    (net (code "50") (name "/DDR2_DQ11") (class "Default")
      (node (ref "J7") (pin "22") (pinfunction "DDR2_DIMM_DQ[11]_22") (pintype "bidirectional"))
      (node (ref "U2") (pin "AP17") (pinfunction "MEMDATA11_AP17") (pintype "bidirectional"))
    )
    (net (code "51") (name "/DDR2_DQ12") (class "Default")
      (node (ref "J7") (pin "131") (pinfunction "DDR2_DIMM_DQ[12]_131") (pintype "bidirectional"))
      (node (ref "U2") (pin "AN20") (pinfunction "MEMDATA12_AN20") (pintype "bidirectional"))
    )
    (net (code "52") (name "/DDR2_DQ13") (class "Default")
      (node (ref "J7") (pin "132") (pinfunction "DDR2_DIMM_DQ[13]_132") (pintype "bidirectional"))
      (node (ref "U2") (pin "AP19") (pinfunction "MEMDATA13_AP19") (pintype "bidirectional"))
    )
    (net (code "53") (name "/DDR2_DQ14") (class "Default")
      (node (ref "J7") (pin "140") (pinfunction "DDR2_DIMM_DQ[14]_140") (pintype "bidirectional"))
      (node (ref "U2") (pin "AN18") (pinfunction "MEMDATA14_AN18") (pintype "bidirectional"))
    )
    (net (code "54") (name "/DDR2_DQ15") (class "Default")
      (node (ref "J7") (pin "141") (pinfunction "DDR2_DIMM_DQ[15]_141") (pintype "bidirectional"))
      (node (ref "U2") (pin "AP18") (pinfunction "MEMDATA15_AP18") (pintype "bidirectional"))
    )
    (net (code "55") (name "/DDR2_DQ16") (class "Default")
      (node (ref "J7") (pin "24") (pinfunction "DDR2_DIMM_DQ[16]_24") (pintype "bidirectional"))
      (node (ref "U2") (pin "AM16") (pinfunction "MEMDATA16_AM16") (pintype "bidirectional"))
    )
    (net (code "56") (name "/DDR2_DQ17") (class "Default")
      (node (ref "J7") (pin "25") (pinfunction "DDR2_DIMM_DQ[17]_25") (pintype "bidirectional"))
      (node (ref "U2") (pin "AP16") (pinfunction "MEMDATA17_AP16") (pintype "bidirectional"))
    )
    (net (code "57") (name "/DDR2_DQ18") (class "Default")
      (node (ref "J7") (pin "30") (pinfunction "DDR2_DIMM_DQ[18]_30") (pintype "bidirectional"))
      (node (ref "U2") (pin "AL15") (pinfunction "MEMDATA18_AL15") (pintype "bidirectional"))
    )
    (net (code "58") (name "/DDR2_DQ19") (class "Default")
      (node (ref "J7") (pin "31") (pinfunction "DDR2_DIMM_DQ[19]_31") (pintype "bidirectional"))
      (node (ref "U2") (pin "AP14") (pinfunction "MEMDATA19_AP14") (pintype "bidirectional"))
    )
    (net (code "59") (name "/DDR2_DQ20") (class "Default")
      (node (ref "J7") (pin "143") (pinfunction "DDR2_DIMM_DQ[20]_143") (pintype "bidirectional"))
      (node (ref "U2") (pin "AL17") (pinfunction "MEMDATA20_AL17") (pintype "bidirectional"))
    )
    (net (code "60") (name "/DDR2_DQ21") (class "Default")
      (node (ref "J7") (pin "144") (pinfunction "DDR2_DIMM_DQ[21]_144") (pintype "bidirectional"))
      (node (ref "U2") (pin "AM17") (pinfunction "MEMDATA21_AM17") (pintype "bidirectional"))
    )
    (net (code "61") (name "/DDR2_DQ22") (class "Default")
      (node (ref "J7") (pin "149") (pinfunction "DDR2_DIMM_DQ[22]_149") (pintype "bidirectional"))
      (node (ref "U2") (pin "AN15") (pinfunction "MEMDATA22_AN15") (pintype "bidirectional"))
    )
    (net (code "62") (name "/DDR2_DQ23") (class "Default")
      (node (ref "J7") (pin "150") (pinfunction "DDR2_DIMM_DQ[23]_150") (pintype "bidirectional"))
      (node (ref "U2") (pin "AM15") (pinfunction "MEMDATA23_AM15") (pintype "bidirectional"))
    )
    (net (code "63") (name "/DDR2_DQ24") (class "Default")
      (node (ref "J7") (pin "33") (pinfunction "DDR2_DIMM_DQ[24]_33") (pintype "bidirectional"))
      (node (ref "U2") (pin "AP13") (pinfunction "MEMDATA24_AP13") (pintype "bidirectional"))
    )
    (net (code "64") (name "/DDR2_DQ25") (class "Default")
      (node (ref "J7") (pin "34") (pinfunction "DDR2_DIMM_DQ[25]_34") (pintype "bidirectional"))
      (node (ref "U2") (pin "AN13") (pinfunction "MEMDATA25_AN13") (pintype "bidirectional"))
    )
    (net (code "65") (name "/DDR2_DQ26") (class "Default")
      (node (ref "J7") (pin "39") (pinfunction "DDR2_DIMM_DQ[26]_39") (pintype "bidirectional"))
      (node (ref "U2") (pin "AP12") (pinfunction "MEMDATA26_AP12") (pintype "bidirectional"))
    )
    (net (code "66") (name "/DDR2_DQ27") (class "Default")
      (node (ref "J7") (pin "40") (pinfunction "DDR2_DIMM_DQ[27]_40") (pintype "bidirectional"))
      (node (ref "U2") (pin "AL12") (pinfunction "MEMDATA27_AL12") (pintype "bidirectional"))
    )
    (net (code "67") (name "/DDR2_DQ28") (class "Default")
      (node (ref "J7") (pin "152") (pinfunction "DDR2_DIMM_DQ[28]_152") (pintype "bidirectional"))
      (node (ref "U2") (pin "AM14") (pinfunction "MEMDATA28_AM14") (pintype "bidirectional"))
    )
    (net (code "68") (name "/DDR2_DQ29") (class "Default")
      (node (ref "J7") (pin "153") (pinfunction "DDR2_DIMM_DQ[29]_153") (pintype "bidirectional"))
      (node (ref "U2") (pin "AN14") (pinfunction "MEMDATA29_AN14") (pintype "bidirectional"))
    )
    (net (code "69") (name "/DDR2_DQ30") (class "Default")
      (node (ref "J7") (pin "158") (pinfunction "DDR2_DIMM_DQ[30]_158") (pintype "bidirectional"))
      (node (ref "U2") (pin "AL13") (pinfunction "MEMDATA30_AL13") (pintype "bidirectional"))
    )
    (net (code "70") (name "/DDR2_DQ31") (class "Default")
      (node (ref "J7") (pin "159") (pinfunction "DDR2_DIMM_DQ[31]_159") (pintype "bidirectional"))
      (node (ref "U2") (pin "AM12") (pinfunction "MEMDATA31_AM12") (pintype "bidirectional"))
    )
    (net (code "71") (name "/DDR2_DQ32") (class "Default")
      (node (ref "J7") (pin "80") (pinfunction "DDR2_DIMM_DQ[32]_80") (pintype "bidirectional"))
      (node (ref "U2") (pin "AF3") (pinfunction "MEMDATA32_AF3") (pintype "bidirectional"))
    )
    (net (code "72") (name "/DDR2_DQ33") (class "Default")
      (node (ref "J7") (pin "81") (pinfunction "DDR2_DIMM_DQ[33]_81") (pintype "bidirectional"))
      (node (ref "U2") (pin "AF1") (pinfunction "MEMDATA33_AF1") (pintype "bidirectional"))
    )
    (net (code "73") (name "/DDR2_DQ34") (class "Default")
      (node (ref "J7") (pin "86") (pinfunction "DDR2_DIMM_DQ[34]_86") (pintype "bidirectional"))
      (node (ref "U2") (pin "AD4") (pinfunction "MEMDATA34_AD4") (pintype "bidirectional"))
    )
    (net (code "74") (name "/DDR2_DQ35") (class "Default")
      (node (ref "J7") (pin "87") (pinfunction "DDR2_DIMM_DQ[35]_87") (pintype "bidirectional"))
      (node (ref "U2") (pin "AD3") (pinfunction "MEMDATA35_AD3") (pintype "bidirectional"))
    )
    (net (code "75") (name "/DDR2_DQ36") (class "Default")
      (node (ref "J7") (pin "199") (pinfunction "DDR2_DIMM_DQ[36]_199") (pintype "bidirectional"))
      (node (ref "U2") (pin "AG3") (pinfunction "MEMDATA36_AG3") (pintype "bidirectional"))
    )
    (net (code "76") (name "/DDR2_DQ37") (class "Default")
      (node (ref "J7") (pin "200") (pinfunction "DDR2_DIMM_DQ[37]_200") (pintype "bidirectional"))
      (node (ref "U2") (pin "AF2") (pinfunction "MEMDATA37_AF2") (pintype "bidirectional"))
    )
    (net (code "77") (name "/DDR2_DQ38") (class "Default")
      (node (ref "J7") (pin "205") (pinfunction "DDR2_DIMM_DQ[38]_205") (pintype "bidirectional"))
      (node (ref "U2") (pin "AE2") (pinfunction "MEMDATA38_AE2") (pintype "bidirectional"))
    )
    (net (code "78") (name "/DDR2_DQ39") (class "Default")
      (node (ref "J7") (pin "206") (pinfunction "DDR2_DIMM_DQ[39]_206") (pintype "bidirectional"))
      (node (ref "U2") (pin "AE1") (pinfunction "MEMDATA39_AE1") (pintype "bidirectional"))
    )
    (net (code "79") (name "/DDR2_DQ40") (class "Default")
      (node (ref "J7") (pin "89") (pinfunction "DDR2_DIMM_DQ[40]_89") (pintype "bidirectional"))
      (node (ref "U2") (pin "AC3") (pinfunction "MEMDATA40_AC3") (pintype "bidirectional"))
    )
    (net (code "80") (name "/DDR2_DQ41") (class "Default")
      (node (ref "J7") (pin "90") (pinfunction "DDR2_DIMM_DQ[41]_90") (pintype "bidirectional"))
      (node (ref "U2") (pin "AC1") (pinfunction "MEMDATA41_AC1") (pintype "bidirectional"))
    )
    (net (code "81") (name "/DDR2_DQ42") (class "Default")
      (node (ref "J7") (pin "95") (pinfunction "DDR2_DIMM_DQ[42]_95") (pintype "bidirectional"))
      (node (ref "U2") (pin "AA4") (pinfunction "MEMDATA42_AA4") (pintype "bidirectional"))
    )
    (net (code "82") (name "/DDR2_DQ43") (class "Default")
      (node (ref "J7") (pin "96") (pinfunction "DDR2_DIMM_DQ[43]_96") (pintype "bidirectional"))
      (node (ref "U2") (pin "AA3") (pinfunction "MEMDATA43_AA3") (pintype "bidirectional"))
    )
    (net (code "83") (name "/DDR2_DQ44") (class "Default")
      (node (ref "J7") (pin "208") (pinfunction "DDR2_DIMM_DQ[44]_208") (pintype "bidirectional"))
      (node (ref "U2") (pin "AD2") (pinfunction "MEMDATA44_AD2") (pintype "bidirectional"))
    )
    (net (code "84") (name "/DDR2_DQ45") (class "Default")
      (node (ref "J7") (pin "209") (pinfunction "DDR2_DIMM_DQ[45]_209") (pintype "bidirectional"))
      (node (ref "U2") (pin "AC4") (pinfunction "MEMDATA45_AC4") (pintype "bidirectional"))
    )
    (net (code "85") (name "/DDR2_DQ46") (class "Default")
      (node (ref "J7") (pin "214") (pinfunction "DDR2_DIMM_DQ[46]_214") (pintype "bidirectional"))
      (node (ref "U2") (pin "AB1") (pinfunction "MEMDATA46_AB1") (pintype "bidirectional"))
    )
    (net (code "86") (name "/DDR2_DQ47") (class "Default")
      (node (ref "J7") (pin "215") (pinfunction "DDR2_DIMM_DQ[47]_215") (pintype "bidirectional"))
      (node (ref "U2") (pin "AB2") (pinfunction "MEMDATA47_AB2") (pintype "bidirectional"))
    )
    (net (code "87") (name "/DDR2_DQ48") (class "Default")
      (node (ref "J7") (pin "98") (pinfunction "DDR2_DIMM_DQ[48]_98") (pintype "bidirectional"))
      (node (ref "U2") (pin "Y3") (pinfunction "MEMDATA48_Y3") (pintype "bidirectional"))
    )
    (net (code "88") (name "/DDR2_DQ49") (class "Default")
      (node (ref "J7") (pin "99") (pinfunction "DDR2_DIMM_DQ[49]_99") (pintype "bidirectional"))
      (node (ref "U2") (pin "Y2") (pinfunction "MEMDATA49_Y2") (pintype "bidirectional"))
    )
    (net (code "89") (name "/DDR2_DQ50") (class "Default")
      (node (ref "J7") (pin "107") (pinfunction "DDR2_DIMM_DQ[50]_107") (pintype "bidirectional"))
      (node (ref "U2") (pin "V4") (pinfunction "MEMDATA50_V4") (pintype "bidirectional"))
    )
    (net (code "90") (name "/DDR2_DQ51") (class "Default")
      (node (ref "J7") (pin "108") (pinfunction "DDR2_DIMM_DQ[51]_108") (pintype "bidirectional"))
      (node (ref "U2") (pin "V3") (pinfunction "MEMDATA51_V3") (pintype "bidirectional"))
    )
    (net (code "91") (name "/DDR2_DQ52") (class "Default")
      (node (ref "J7") (pin "217") (pinfunction "DDR2_DIMM_DQ[52]_217") (pintype "bidirectional"))
      (node (ref "U2") (pin "AA2") (pinfunction "MEMDATA52_AA2") (pintype "bidirectional"))
    )
    (net (code "92") (name "/DDR2_DQ53") (class "Default")
      (node (ref "J7") (pin "218") (pinfunction "DDR2_DIMM_DQ[53]_218") (pintype "bidirectional"))
      (node (ref "U2") (pin "AA1") (pinfunction "MEMDATA53_AA1") (pintype "bidirectional"))
    )
    (net (code "93") (name "/DDR2_DQ54") (class "Default")
      (node (ref "J7") (pin "226") (pinfunction "DDR2_DIMM_DQ[54]_226") (pintype "bidirectional"))
      (node (ref "U2") (pin "W3") (pinfunction "MEMDATA54_W3") (pintype "bidirectional"))
    )
    (net (code "94") (name "/DDR2_DQ55") (class "Default")
      (node (ref "J7") (pin "227") (pinfunction "DDR2_DIMM_DQ[55]_227") (pintype "bidirectional"))
      (node (ref "U2") (pin "W1") (pinfunction "MEMDATA55_W1") (pintype "bidirectional"))
    )
    (net (code "95") (name "/DDR2_DQ56") (class "Default")
      (node (ref "J7") (pin "110") (pinfunction "DDR2_DIMM_DQ[56]_110") (pintype "bidirectional"))
      (node (ref "U2") (pin "U1") (pinfunction "MEMDATA56_U1") (pintype "bidirectional"))
    )
    (net (code "96") (name "/DDR2_DQ57") (class "Default")
      (node (ref "J7") (pin "111") (pinfunction "DDR2_DIMM_DQ[57]_111") (pintype "bidirectional"))
      (node (ref "U2") (pin "U2") (pinfunction "MEMDATA57_U2") (pintype "bidirectional"))
    )
    (net (code "97") (name "/DDR2_DQ58") (class "Default")
      (node (ref "J7") (pin "116") (pinfunction "DDR2_DIMM_DQ[58]_116") (pintype "bidirectional"))
      (node (ref "U2") (pin "T4") (pinfunction "MEMDATA58_T4") (pintype "bidirectional"))
    )
    (net (code "98") (name "/DDR2_DQ59") (class "Default")
      (node (ref "J7") (pin "117") (pinfunction "DDR2_DIMM_DQ[59]_117") (pintype "bidirectional"))
      (node (ref "U2") (pin "R1") (pinfunction "MEMDATA59_R1") (pintype "bidirectional"))
    )
    (net (code "99") (name "/DDR2_DQ60") (class "Default")
      (node (ref "J7") (pin "229") (pinfunction "DDR2_DIMM_DQ[60]_229") (pintype "bidirectional"))
      (node (ref "U2") (pin "V2") (pinfunction "MEMDATA60_V2") (pintype "bidirectional"))
    )
    (net (code "100") (name "/DDR2_DQ61") (class "Default")
      (node (ref "J7") (pin "230") (pinfunction "DDR2_DIMM_DQ[61]_230") (pintype "bidirectional"))
      (node (ref "U2") (pin "V1") (pinfunction "MEMDATA61_V1") (pintype "bidirectional"))
    )
    (net (code "101") (name "/DDR2_DQ62") (class "Default")
      (node (ref "J7") (pin "235") (pinfunction "DDR2_DIMM_DQ[62]_235") (pintype "bidirectional"))
      (node (ref "U2") (pin "T1") (pinfunction "MEMDATA62_T1") (pintype "bidirectional"))
    )
    (net (code "102") (name "/DDR2_DQ63") (class "Default")
      (node (ref "J7") (pin "236") (pinfunction "DDR2_DIMM_DQ[63]_236") (pintype "bidirectional"))
      (node (ref "U2") (pin "T3") (pinfunction "MEMDATA63_T3") (pintype "bidirectional"))
    )
    (net (code "103") (name "/DDR2_DQ64") (class "Default")
      (node (ref "J7") (pin "42") (pinfunction "DDR2_DIMM_CB0_42") (pintype "bidirectional"))
      (node (ref "U2") (pin "AM11") (pinfunction "ECC0_AM11") (pintype "bidirectional"))
    )
    (net (code "104") (name "/DDR2_DQ65") (class "Default")
      (node (ref "J7") (pin "43") (pinfunction "DDR2_DIMM_CB1_43") (pintype "bidirectional"))
      (node (ref "U2") (pin "AL11") (pinfunction "ECC1_AL11") (pintype "bidirectional"))
    )
    (net (code "105") (name "/DDR2_DQ66") (class "Default")
      (node (ref "J7") (pin "48") (pinfunction "DDR2_DIMM_CB2_48") (pintype "bidirectional"))
      (node (ref "U2") (pin "AM9") (pinfunction "ECC2_AM9") (pintype "bidirectional"))
    )
    (net (code "106") (name "/DDR2_DQ67") (class "Default")
      (node (ref "J7") (pin "49") (pinfunction "DDR2_DIMM_CB3_49") (pintype "bidirectional"))
      (node (ref "U2") (pin "AL9") (pinfunction "ECC3_AL9") (pintype "bidirectional"))
    )
    (net (code "107") (name "/DDR2_DQ68") (class "Default")
      (node (ref "J7") (pin "161") (pinfunction "DDR2_DIMM_CB4_161") (pintype "bidirectional"))
      (node (ref "U2") (pin "AP11") (pinfunction "ECC4_AP11") (pintype "bidirectional"))
    )
    (net (code "108") (name "/DDR2_DQ69") (class "Default")
      (node (ref "J7") (pin "162") (pinfunction "DDR2_DIMM_CB5_162") (pintype "bidirectional"))
      (node (ref "U2") (pin "AN11") (pinfunction "ECC5_AN11") (pintype "bidirectional"))
    )
    (net (code "109") (name "/DDR2_DQ70") (class "Default")
      (node (ref "J7") (pin "167") (pinfunction "DDR2_DIMM_CB6_167") (pintype "bidirectional"))
      (node (ref "U2") (pin "AM10") (pinfunction "ECC6_AM10") (pintype "bidirectional"))
    )
    (net (code "110") (name "/DDR2_DQ71") (class "Default")
      (node (ref "J7") (pin "168") (pinfunction "DDR2_DIMM_CB7_168") (pintype "bidirectional"))
      (node (ref "U2") (pin "AP9") (pinfunction "ECC7_AP9") (pintype "bidirectional"))
    )
    (net (code "111") (name "/DDR2_DQS0") (class "Default")
      (node (ref "J7") (pin "7") (pinfunction "DDR2_DIMM_DQS_P[0]_7") (pintype "bidirectional"))
      (node (ref "U2") (pin "AM21") (pinfunction "DQS0_AM21") (pintype "bidirectional"))
    )
    (net (code "112") (name "/DDR2_DQS1") (class "Default")
      (node (ref "J7") (pin "16") (pinfunction "DDR2_DIMM_DQS_P[1]_16") (pintype "bidirectional"))
      (node (ref "U2") (pin "AM19") (pinfunction "DQS1_AM19") (pintype "bidirectional"))
    )
    (net (code "113") (name "/DDR2_DQS2") (class "Default")
      (node (ref "J7") (pin "28") (pinfunction "DDR2_DIMM_DQS_P[2]_28") (pintype "bidirectional"))
      (node (ref "U2") (pin "AL16") (pinfunction "DQS2_AL16") (pintype "bidirectional"))
    )
    (net (code "114") (name "/DDR2_DQS3") (class "Default")
      (node (ref "J7") (pin "37") (pinfunction "DDR2_DIMM_DQS_P[3]_37") (pintype "bidirectional"))
      (node (ref "U2") (pin "AM13") (pinfunction "DQS3_AM13") (pintype "bidirectional"))
    )
    (net (code "115") (name "/DDR2_DQS4") (class "Default")
      (node (ref "J7") (pin "84") (pinfunction "DDR2_DIMM_DQS_P[4]_84") (pintype "bidirectional"))
      (node (ref "U2") (pin "AE3") (pinfunction "DQS4_AE3") (pintype "bidirectional"))
    )
    (net (code "116") (name "/DDR2_DQS5") (class "Default")
      (node (ref "J7") (pin "93") (pinfunction "DDR2_DIMM_DQS_P[5]_93") (pintype "bidirectional"))
      (node (ref "U2") (pin "AB4") (pinfunction "DQS5_AB4") (pintype "bidirectional"))
    )
    (net (code "117") (name "/DDR2_DQS6") (class "Default")
      (node (ref "J7") (pin "105") (pinfunction "DDR2_DIMM_DQS_P[6]_105") (pintype "bidirectional"))
      (node (ref "U2") (pin "W4") (pinfunction "DQS6_W4") (pintype "bidirectional"))
    )
    (net (code "118") (name "/DDR2_DQS7") (class "Default")
      (node (ref "J7") (pin "114") (pinfunction "DDR2_DIMM_DQS_P[7]_114") (pintype "bidirectional"))
      (node (ref "U2") (pin "U4") (pinfunction "DQS7_U4") (pintype "bidirectional"))
    )
    (net (code "119") (name "/DDR2_DQS8") (class "Default")
      (node (ref "J7") (pin "46") (pinfunction "DDR2_DIMM_DQS_CB_P_46") (pintype "bidirectional"))
      (node (ref "U2") (pin "AP10") (pinfunction "DQS8_AP10") (pintype "bidirectional"))
    )
    (net (code "120") (name "/DDR2_ODT0") (class "Default")
      (node (ref "J7") (pin "195") (pinfunction "DDR2_DIMM_ODT[0]_195") (pintype "input"))
      (node (ref "R142") (pin "1") (pinfunction "1_1") (pintype "passive"))
      (node (ref "RP7") (pin "2") (pinfunction "2_2") (pintype "passive"))
      (node (ref "U2") (pin "AH3") (pinfunction "MEMODT0_AH3") (pintype "output"))
    )
    (net (code "121") (name "/DDR2_ODT1") (class "Default")
      (node (ref "J7") (pin "77") (pinfunction "DDR2_DIMM_ODT[1]_77") (pintype "input"))
      (node (ref "R143") (pin "1") (pinfunction "1_1") (pintype "passive"))
      (node (ref "RP7") (pin "4") (pinfunction "4_4") (pintype "passive"))
      (node (ref "U2") (pin "AG1") (pinfunction "MEMODT1_AG1") (pintype "output"))
    )
    (net (code "122") (name "/DDR2_RASn") (class "Default")
      (node (ref "J7") (pin "192") (pinfunction "DDR2_DIMM_RAS#_192") (pintype "input"))
      (node (ref "RP6") (pin "1") (pinfunction "1_1") (pintype "passive"))
      (node (ref "U2") (pin "AJ4") (pinfunction "RAS#_AJ4") (pintype "output"))
    )
    (net (code "123") (name "/DDR2_Sn0") (class "Default")
      (node (ref "J7") (pin "193") (pinfunction "DDR2_DIMM_S#[0]_193") (pintype "input"))
      (node (ref "RP6") (pin "3") (pinfunction "3_3") (pintype "passive"))
      (node (ref "U2") (pin "AH2") (pinfunction "BANKSEL#0_AH2") (pintype "output"))
    )
    (net (code "124") (name "/DDR2_Sn1") (class "Default")
      (node (ref "J7") (pin "76") (pinfunction "DDR2_DIMM_S#[1]_76") (pintype "input"))
      (node (ref "RP7") (pin "1") (pinfunction "1_1") (pintype "passive"))
      (node (ref "U2") (pin "AH1") (pinfunction "BANKSEL#1_AH1") (pintype "output"))
    )
    (net (code "125") (name "/DDR2_WEn") (class "Default")
      (node (ref "J7") (pin "73") (pinfunction "DDR2_DIMM_WE#_73") (pintype "input"))
      (node (ref "RP6") (pin "2") (pinfunction "2_2") (pintype "passive"))
      (node (ref "U2") (pin "AJ2") (pinfunction "WE#_AJ2") (pintype "output"))
    )
    (net (code "126") (name "/PPC_SCL") (class "Default")
      (node (ref "J7") (pin "120") (pinfunction "DDR2_DIMM_SCL_120") (pintype "input"))
    )
    (net (code "127") (name "/PPC_SDA") (class "Default")
      (node (ref "J7") (pin "119") (pinfunction "DDR2_DIMM_SDA_119") (pintype "bidirectional"))
    )
    (net (code "128") (name "/SYS_PORn") (class "Default")
      (node (ref "J7") (pin "18") (pinfunction "DDR2_DIMM_RESET#_18") (pintype "input"))
    )
    (net (code "129") (name "1V8") (class "Default")
      (node (ref "C198") (pin "2") (pinfunction "2_2") (pintype "passive"))
      (node (ref "C205") (pin "2") (pinfunction "2_2") (pintype "passive"))
      (node (ref "C206") (pin "2") (pinfunction "2_2") (pintype "passive"))
      (node (ref "C207") (pin "2") (pinfunction "2_2") (pintype "passive"))
      (node (ref "C208") (pin "2") (pinfunction "2_2") (pintype "passive"))
      (node (ref "C209") (pin "2") (pinfunction "2_2") (pintype "passive"))
      (node (ref "C210") (pin "2") (pinfunction "2_2") (pintype "passive"))
      (node (ref "C211") (pin "2") (pinfunction "2_2") (pintype "passive"))
      (node (ref "C212") (pin "2") (pinfunction "2_2") (pintype "passive"))
      (node (ref "C213") (pin "2") (pinfunction "2_2") (pintype "passive"))
      (node (ref "C214") (pin "2") (pinfunction "2_2") (pintype "passive"))
      (node (ref "C215") (pin "2") (pinfunction "2_2") (pintype "passive"))
      (node (ref "C216") (pin "2") (pinfunction "2_2") (pintype "passive"))
      (node (ref "C218") (pin "1") (pinfunction "1_1") (pintype "passive"))
      (node (ref "C219") (pin "1") (pinfunction "1_1") (pintype "passive"))
      (node (ref "C221") (pin "2") (pinfunction "2_2") (pintype "passive"))
      (node (ref "C222") (pin "2") (pinfunction "2_2") (pintype "passive"))
      (node (ref "C223") (pin "2") (pinfunction "2_2") (pintype "passive"))
      (node (ref "C224") (pin "2") (pinfunction "2_2") (pintype "passive"))
      (node (ref "C225") (pin "2") (pinfunction "2_2") (pintype "passive"))
      (node (ref "C226") (pin "2") (pinfunction "2_2") (pintype "passive"))
      (node (ref "C227") (pin "2") (pinfunction "2_2") (pintype "passive"))
      (node (ref "C228") (pin "2") (pinfunction "2_2") (pintype "passive"))
      (node (ref "C229") (pin "2") (pinfunction "2_2") (pintype "passive"))
      (node (ref "C230") (pin "2") (pinfunction "2_2") (pintype "passive"))
      (node (ref "J7") (pin "170") (pinfunction "VDDQ_7_170") (pintype "power_in"))
      (node (ref "J7") (pin "172") (pinfunction "VDD_6_172") (pintype "power_in"))
      (node (ref "J7") (pin "175") (pinfunction "VDDQ_8_175") (pintype "power_in"))
      (node (ref "J7") (pin "178") (pinfunction "VDD_7_178") (pintype "power_in"))
      (node (ref "J7") (pin "181") (pinfunction "VDDQ_9_181") (pintype "power_in"))
      (node (ref "J7") (pin "184") (pinfunction "VDD_8_184") (pintype "power_in"))
      (node (ref "J7") (pin "187") (pinfunction "VDD_9_187") (pintype "power_in"))
      (node (ref "J7") (pin "189") (pinfunction "VDD_10_189") (pintype "power_in"))
      (node (ref "J7") (pin "191") (pinfunction "VDDQ_10_191") (pintype "power_in"))
      (node (ref "J7") (pin "194") (pinfunction "VDDQ_11_194") (pintype "power_in"))
      (node (ref "J7") (pin "197") (pinfunction "VDD_11_197") (pintype "power_in"))
      (node (ref "J7") (pin "51") (pinfunction "VDDQ_1_51") (pintype "power_in"))
      (node (ref "J7") (pin "53") (pinfunction "VDD_1_53") (pintype "power_in"))
      (node (ref "J7") (pin "56") (pinfunction "VDDQ_2_56") (pintype "power_in"))
      (node (ref "J7") (pin "59") (pinfunction "VDD_2_59") (pintype "power_in"))
      (node (ref "J7") (pin "62") (pinfunction "VDDQ_3_62") (pintype "power_in"))
      (node (ref "J7") (pin "64") (pinfunction "VDD_3_64") (pintype "power_in"))
      (node (ref "J7") (pin "67") (pinfunction "VDD_4_67") (pintype "power_in"))
      (node (ref "J7") (pin "69") (pinfunction "VDD_5_69") (pintype "power_in"))
      (node (ref "J7") (pin "72") (pinfunction "VDDQ_4_72") (pintype "power_in"))
      (node (ref "J7") (pin "75") (pinfunction "VDDQ_5_75") (pintype "power_in"))
      (node (ref "J7") (pin "78") (pinfunction "VDDQ_6_78") (pintype "power_in"))
      (node (ref "L19") (pin "1") (pinfunction "1_1") (pintype "passive"))
      (node (ref "R144") (pin "1") (pinfunction "1_1") (pintype "passive"))
      (node (ref "U38") (pin "1") (pinfunction "VDDQ1_1") (pintype "input"))
      (node (ref "U38") (pin "15") (pinfunction "VDDQ4_15") (pintype "input"))
      (node (ref "U38") (pin "20") (pinfunction "VDDQ5_20") (pintype "input"))
      (node (ref "U38") (pin "21") (pinfunction "OS_21") (pintype "input"))
      (node (ref "U38") (pin "23") (pinfunction "VDDQ6_23") (pintype "input"))
      (node (ref "U38") (pin "28") (pinfunction "VDDQ7_28") (pintype "input"))
      (node (ref "U38") (pin "31") (pinfunction "VDDQ8_31") (pintype "input"))
      (node (ref "U38") (pin "36") (pinfunction "VDDQ9_36") (pintype "input"))
      (node (ref "U38") (pin "6") (pinfunction "VDDQ2_6") (pintype "input"))
      (node (ref "U38") (pin "9") (pinfunction "VDDQ3_9") (pintype "input"))
      (node (ref "U39") (pin "1") (pinfunction "VDDQSNS_1") (pintype "input"))
      (node (ref "U39") (pin "2") (pinfunction "VLDOIN_2") (pintype "input"))
    )
    (net (code "130") (name "3V3") (class "Default")
      (node (ref "J7") (pin "238") (pinfunction "VDDSPD_238") (pintype "power_in"))
    )
    (net (code "131") (name "5V") (class "Default")
      (node (ref "C217") (pin "1") (pinfunction "1_1") (pintype "passive"))
      (node (ref "R146") (pin "1") (pinfunction "1_1") (pintype "passive"))
      (node (ref "R148") (pin "2") (pinfunction "2_2") (pintype "passive"))
      (node (ref "U39") (pin "10") (pinfunction "VIN_10") (pintype "input"))
    )
    (net (code "132") (name "DDR2_VREF") (class "Default")
      (node (ref "C198") (pin "1") (pinfunction "1_1") (pintype "passive"))
      (node (ref "C200") (pin "1") (pinfunction "1_1") (pintype "passive"))
      (node (ref "C201") (pin "1") (pinfunction "1_1") (pintype "passive"))
      (node (ref "C202") (pin "1") (pinfunction "1_1") (pintype "passive"))
      (node (ref "C203") (pin "1") (pinfunction "1_1") (pintype "passive"))
      (node (ref "C231") (pin "2") (pinfunction "2_2") (pintype "passive"))
      (node (ref "C232") (pin "2") (pinfunction "2_2") (pintype "passive"))
      (node (ref "C234") (pin "2") (pinfunction "2_2") (pintype "passive"))
      (node (ref "J7") (pin "1") (pinfunction "VREF_1") (pintype "power_in"))
      (node (ref "U2") (pin "AF4") (pinfunction "SVREF2A_AF4") (pintype "input"))
      (node (ref "U2") (pin "AL10") (pinfunction "SVREF1B_AL10") (pintype "input"))
      (node (ref "U2") (pin "AL19") (pinfunction "SVREF2B_AL19") (pintype "input"))
      (node (ref "U2") (pin "Y4") (pinfunction "SVREF1A_Y4") (pintype "input"))
      (node (ref "U39") (pin "6") (pinfunction "VTTREF_6") (pintype "output"))
    )
    (net (code "133") (name "DDR2_VTT") (class "Default")
      (node (ref "C204") (pin "1") (pinfunction "1_1") (pintype "passive"))
      (node (ref "C220") (pin "1") (pinfunction "1_1") (pintype "passive"))
      (node (ref "C235") (pin "1") (pinfunction "1_1") (pintype "passive"))
      (node (ref "C236") (pin "1") (pinfunction "1_1") (pintype "passive"))
      (node (ref "CP1") (pin "1") (pinfunction "1_1") (pintype "passive"))
      (node (ref "CP1") (pin "2") (pinfunction "2_2") (pintype "passive"))
      (node (ref "CP1") (pin "3") (pinfunction "3_3") (pintype "passive"))
      (node (ref "CP1") (pin "4") (pinfunction "4_4") (pintype "passive"))
      (node (ref "CP2") (pin "1") (pinfunction "1_1") (pintype "passive"))
      (node (ref "CP2") (pin "2") (pinfunction "2_2") (pintype "passive"))
      (node (ref "CP2") (pin "3") (pinfunction "3_3") (pintype "passive"))
      (node (ref "CP2") (pin "4") (pinfunction "4_4") (pintype "passive"))
      (node (ref "CP3") (pin "1") (pinfunction "1_1") (pintype "passive"))
      (node (ref "CP3") (pin "2") (pinfunction "2_2") (pintype "passive"))
      (node (ref "CP3") (pin "3") (pinfunction "3_3") (pintype "passive"))
      (node (ref "CP3") (pin "4") (pinfunction "4_4") (pintype "passive"))
      (node (ref "CP4") (pin "1") (pinfunction "1_1") (pintype "passive"))
      (node (ref "CP4") (pin "2") (pinfunction "2_2") (pintype "passive"))
      (node (ref "CP4") (pin "3") (pinfunction "3_3") (pintype "passive"))
      (node (ref "CP4") (pin "4") (pinfunction "4_4") (pintype "passive"))
      (node (ref "CP5") (pin "1") (pinfunction "1_1") (pintype "passive"))
      (node (ref "CP5") (pin "2") (pinfunction "2_2") (pintype "passive"))
      (node (ref "CP5") (pin "3") (pinfunction "3_3") (pintype "passive"))
      (node (ref "CP5") (pin "4") (pinfunction "4_4") (pintype "passive"))
      (node (ref "CP6") (pin "1") (pinfunction "1_1") (pintype "passive"))
      (node (ref "CP6") (pin "2") (pinfunction "2_2") (pintype "passive"))
      (node (ref "CP6") (pin "3") (pinfunction "3_3") (pintype "passive"))
      (node (ref "CP6") (pin "4") (pinfunction "4_4") (pintype "passive"))
      (node (ref "CP7") (pin "1") (pinfunction "1_1") (pintype "passive"))
      (node (ref "CP7") (pin "2") (pinfunction "2_2") (pintype "passive"))
      (node (ref "CP7") (pin "3") (pinfunction "3_3") (pintype "passive"))
      (node (ref "CP7") (pin "4") (pinfunction "4_4") (pintype "passive"))
      (node (ref "R147") (pin "1") (pinfunction "1_1") (pintype "passive"))
      (node (ref "RP1") (pin "5") (pinfunction "5_5") (pintype "passive"))
      (node (ref "RP1") (pin "6") (pinfunction "6_6") (pintype "passive"))
      (node (ref "RP1") (pin "7") (pinfunction "7_7") (pintype "passive"))
      (node (ref "RP1") (pin "8") (pinfunction "8_8") (pintype "passive"))
      (node (ref "RP2") (pin "5") (pinfunction "5_5") (pintype "passive"))
      (node (ref "RP2") (pin "6") (pinfunction "6_6") (pintype "passive"))
      (node (ref "RP2") (pin "7") (pinfunction "7_7") (pintype "passive"))
      (node (ref "RP2") (pin "8") (pinfunction "8_8") (pintype "passive"))
      (node (ref "RP3") (pin "5") (pinfunction "5_5") (pintype "passive"))
      (node (ref "RP3") (pin "6") (pinfunction "6_6") (pintype "passive"))
      (node (ref "RP3") (pin "7") (pinfunction "7_7") (pintype "passive"))
      (node (ref "RP3") (pin "8") (pinfunction "8_8") (pintype "passive"))
      (node (ref "RP4") (pin "5") (pinfunction "5_5") (pintype "passive"))
      (node (ref "RP4") (pin "6") (pinfunction "6_6") (pintype "passive"))
      (node (ref "RP4") (pin "7") (pinfunction "7_7") (pintype "passive"))
      (node (ref "RP4") (pin "8") (pinfunction "8_8") (pintype "passive"))
      (node (ref "RP5") (pin "5") (pinfunction "5_5") (pintype "passive"))
      (node (ref "RP5") (pin "6") (pinfunction "6_6") (pintype "passive"))
      (node (ref "RP5") (pin "7") (pinfunction "7_7") (pintype "passive"))
      (node (ref "RP5") (pin "8") (pinfunction "8_8") (pintype "passive"))
      (node (ref "RP6") (pin "5") (pinfunction "5_5") (pintype "passive"))
      (node (ref "RP6") (pin "6") (pinfunction "6_6") (pintype "passive"))
      (node (ref "RP6") (pin "7") (pinfunction "7_7") (pintype "passive"))
      (node (ref "RP6") (pin "8") (pinfunction "8_8") (pintype "passive"))
      (node (ref "RP7") (pin "5") (pinfunction "5_5") (pintype "passive"))
      (node (ref "RP7") (pin "6") (pinfunction "6_6") (pintype "passive"))
      (node (ref "RP7") (pin "7") (pinfunction "7_7") (pintype "passive"))
      (node (ref "RP7") (pin "8") (pinfunction "8_8") (pintype "passive"))
      (node (ref "U39") (pin "3") (pinfunction "VTT_3") (pintype "output"))
    )
    (net (code "134") (name "GND") (class "Default")
      (node (ref "C178") (pin "1") (pinfunction "1_1") (pintype "passive"))
      (node (ref "C193") (pin "2") (pinfunction "2_2") (pintype "passive"))
      (node (ref "C194") (pin "1") (pinfunction "1_1") (pintype "passive"))
      (node (ref "C195") (pin "1") (pinfunction "1_1") (pintype "passive"))
      (node (ref "C200") (pin "2") (pinfunction "2_2") (pintype "passive"))
      (node (ref "C201") (pin "2") (pinfunction "2_2") (pintype "passive"))
      (node (ref "C202") (pin "2") (pinfunction "2_2") (pintype "passive"))
      (node (ref "C203") (pin "2") (pinfunction "2_2") (pintype "passive"))
      (node (ref "C204") (pin "2") (pinfunction "2_2") (pintype "passive"))
      (node (ref "C205") (pin "1") (pinfunction "1_1") (pintype "passive"))
      (node (ref "C206") (pin "1") (pinfunction "1_1") (pintype "passive"))
      (node (ref "C207") (pin "1") (pinfunction "1_1") (pintype "passive"))
      (node (ref "C208") (pin "1") (pinfunction "1_1") (pintype "passive"))
      (node (ref "C209") (pin "1") (pinfunction "1_1") (pintype "passive"))
      (node (ref "C210") (pin "1") (pinfunction "1_1") (pintype "passive"))
      (node (ref "C211") (pin "1") (pinfunction "1_1") (pintype "passive"))
      (node (ref "C212") (pin "1") (pinfunction "1_1") (pintype "passive"))
      (node (ref "C213") (pin "1") (pinfunction "1_1") (pintype "passive"))
      (node (ref "C214") (pin "1") (pinfunction "1_1") (pintype "passive"))
      (node (ref "C215") (pin "1") (pinfunction "1_1") (pintype "passive"))
      (node (ref "C216") (pin "1") (pinfunction "1_1") (pintype "passive"))
      (node (ref "C217") (pin "2") (pinfunction "2_2") (pintype "passive"))
      (node (ref "C218") (pin "2") (pinfunction "2_2") (pintype "passive"))
      (node (ref "C219") (pin "2") (pinfunction "2_2") (pintype "passive"))
      (node (ref "C220") (pin "2") (pinfunction "2_2") (pintype "passive"))
      (node (ref "C221") (pin "1") (pinfunction "1_1") (pintype "passive"))
      (node (ref "C222") (pin "1") (pinfunction "1_1") (pintype "passive"))
      (node (ref "C223") (pin "1") (pinfunction "1_1") (pintype "passive"))
      (node (ref "C224") (pin "1") (pinfunction "1_1") (pintype "passive"))
      (node (ref "C225") (pin "1") (pinfunction "1_1") (pintype "passive"))
      (node (ref "C226") (pin "1") (pinfunction "1_1") (pintype "passive"))
      (node (ref "C227") (pin "1") (pinfunction "1_1") (pintype "passive"))
      (node (ref "C228") (pin "1") (pinfunction "1_1") (pintype "passive"))
      (node (ref "C229") (pin "1") (pinfunction "1_1") (pintype "passive"))
      (node (ref "C230") (pin "1") (pinfunction "1_1") (pintype "passive"))
      (node (ref "C231") (pin "1") (pinfunction "1_1") (pintype "passive"))
      (node (ref "C232") (pin "1") (pinfunction "1_1") (pintype "passive"))
      (node (ref "C234") (pin "1") (pinfunction "1_1") (pintype "passive"))
      (node (ref "C235") (pin "2") (pinfunction "2_2") (pintype "passive"))
      (node (ref "C236") (pin "2") (pinfunction "2_2") (pintype "passive"))
      (node (ref "CP1") (pin "5") (pinfunction "5_5") (pintype "passive"))
      (node (ref "CP1") (pin "6") (pinfunction "6_6") (pintype "passive"))
      (node (ref "CP1") (pin "7") (pinfunction "7_7") (pintype "passive"))
      (node (ref "CP1") (pin "8") (pinfunction "8_8") (pintype "passive"))
      (node (ref "CP2") (pin "5") (pinfunction "5_5") (pintype "passive"))
      (node (ref "CP2") (pin "6") (pinfunction "6_6") (pintype "passive"))
      (node (ref "CP2") (pin "7") (pinfunction "7_7") (pintype "passive"))
      (node (ref "CP2") (pin "8") (pinfunction "8_8") (pintype "passive"))
      (node (ref "CP3") (pin "5") (pinfunction "5_5") (pintype "passive"))
      (node (ref "CP3") (pin "6") (pinfunction "6_6") (pintype "passive"))
      (node (ref "CP3") (pin "7") (pinfunction "7_7") (pintype "passive"))
      (node (ref "CP3") (pin "8") (pinfunction "8_8") (pintype "passive"))
      (node (ref "CP4") (pin "5") (pinfunction "5_5") (pintype "passive"))
      (node (ref "CP4") (pin "6") (pinfunction "6_6") (pintype "passive"))
      (node (ref "CP4") (pin "7") (pinfunction "7_7") (pintype "passive"))
      (node (ref "CP4") (pin "8") (pinfunction "8_8") (pintype "passive"))
      (node (ref "CP5") (pin "5") (pinfunction "5_5") (pintype "passive"))
      (node (ref "CP5") (pin "6") (pinfunction "6_6") (pintype "passive"))
      (node (ref "CP5") (pin "7") (pinfunction "7_7") (pintype "passive"))
      (node (ref "CP5") (pin "8") (pinfunction "8_8") (pintype "passive"))
      (node (ref "CP6") (pin "5") (pinfunction "5_5") (pintype "passive"))
      (node (ref "CP6") (pin "6") (pinfunction "6_6") (pintype "passive"))
      (node (ref "CP6") (pin "7") (pinfunction "7_7") (pintype "passive"))
      (node (ref "CP6") (pin "8") (pinfunction "8_8") (pintype "passive"))
      (node (ref "CP7") (pin "5") (pinfunction "5_5") (pintype "passive"))
      (node (ref "CP7") (pin "6") (pinfunction "6_6") (pintype "passive"))
      (node (ref "CP7") (pin "7") (pinfunction "7_7") (pintype "passive"))
      (node (ref "CP7") (pin "8") (pinfunction "8_8") (pintype "passive"))
      (node (ref "J7") (pin "100") (pinfunction "VSS_27_100") (pintype "power_in"))
      (node (ref "J7") (pin "101") (pinfunction "DDR2_DIMM_SA2_101") (pintype "input"))
      (node (ref "J7") (pin "103") (pinfunction "VSS_28_103") (pintype "power_in"))
      (node (ref "J7") (pin "106") (pinfunction "VSS_29_106") (pintype "power_in"))
      (node (ref "J7") (pin "109") (pinfunction "VSS_30_109") (pintype "power_in"))
      (node (ref "J7") (pin "11") (pinfunction "VSS_4_11") (pintype "power_in"))
      (node (ref "J7") (pin "112") (pinfunction "VSS_31_112") (pintype "power_in"))
      (node (ref "J7") (pin "115") (pinfunction "VSS_32_115") (pintype "power_in"))
      (node (ref "J7") (pin "118") (pinfunction "VSS_33_118") (pintype "power_in"))
      (node (ref "J7") (pin "121") (pinfunction "VSS_34_121") (pintype "power_in"))
      (node (ref "J7") (pin "124") (pinfunction "VSS_35_124") (pintype "power_in"))
      (node (ref "J7") (pin "127") (pinfunction "VSS_36_127") (pintype "power_in"))
      (node (ref "J7") (pin "130") (pinfunction "VSS_37_130") (pintype "power_in"))
      (node (ref "J7") (pin "133") (pinfunction "VSS_38_133") (pintype "power_in"))
      (node (ref "J7") (pin "136") (pinfunction "VSS_39_136") (pintype "power_in"))
      (node (ref "J7") (pin "139") (pinfunction "VSS_40_139") (pintype "power_in"))
      (node (ref "J7") (pin "14") (pinfunction "VSS_5_14") (pintype "power_in"))
      (node (ref "J7") (pin "142") (pinfunction "VSS_41_142") (pintype "power_in"))
      (node (ref "J7") (pin "145") (pinfunction "VSS_42_145") (pintype "power_in"))
      (node (ref "J7") (pin "148") (pinfunction "VSS_43_148") (pintype "power_in"))
      (node (ref "J7") (pin "151") (pinfunction "VSS_44_151") (pintype "power_in"))
      (node (ref "J7") (pin "154") (pinfunction "VSS_45_154") (pintype "power_in"))
      (node (ref "J7") (pin "157") (pinfunction "VSS_46_157") (pintype "power_in"))
      (node (ref "J7") (pin "160") (pinfunction "VSS_47_160") (pintype "power_in"))
      (node (ref "J7") (pin "163") (pinfunction "VSS_48_163") (pintype "power_in"))
      (node (ref "J7") (pin "166") (pinfunction "VSS_49_166") (pintype "power_in"))
      (node (ref "J7") (pin "169") (pinfunction "VSS_50_169") (pintype "power_in"))
      (node (ref "J7") (pin "17") (pinfunction "VSS_6_17") (pintype "power_in"))
      (node (ref "J7") (pin "198") (pinfunction "VSS_51_198") (pintype "power_in"))
      (node (ref "J7") (pin "2") (pinfunction "VSS_1_2") (pintype "power_in"))
      (node (ref "J7") (pin "20") (pinfunction "VSS_7_20") (pintype "power_in"))
      (node (ref "J7") (pin "201") (pinfunction "VSS_52_201") (pintype "power_in"))
      (node (ref "J7") (pin "204") (pinfunction "VSS_53_204") (pintype "power_in"))
      (node (ref "J7") (pin "207") (pinfunction "VSS_54_207") (pintype "power_in"))
      (node (ref "J7") (pin "210") (pinfunction "VSS_55_210") (pintype "power_in"))
      (node (ref "J7") (pin "213") (pinfunction "VSS_56_213") (pintype "power_in"))
      (node (ref "J7") (pin "216") (pinfunction "VSS_57_216") (pintype "power_in"))
      (node (ref "J7") (pin "219") (pinfunction "VSS_58_219") (pintype "power_in"))
      (node (ref "J7") (pin "222") (pinfunction "VSS_59_222") (pintype "power_in"))
      (node (ref "J7") (pin "225") (pinfunction "VSS_60_225") (pintype "power_in"))
      (node (ref "J7") (pin "228") (pinfunction "VSS_61_228") (pintype "power_in"))
      (node (ref "J7") (pin "23") (pinfunction "VSS_8_23") (pintype "power_in"))
      (node (ref "J7") (pin "231") (pinfunction "VSS_62_231") (pintype "power_in"))
      (node (ref "J7") (pin "234") (pinfunction "VSS_63_234") (pintype "power_in"))
      (node (ref "J7") (pin "237") (pinfunction "VSS_64_237") (pintype "power_in"))
      (node (ref "J7") (pin "239") (pinfunction "DDR2_DIMM_SA0_239") (pintype "input"))
      (node (ref "J7") (pin "240") (pinfunction "DDR2_DIMM_SA1_240") (pintype "input"))
      (node (ref "J7") (pin "26") (pinfunction "VSS_9_26") (pintype "power_in"))
      (node (ref "J7") (pin "29") (pinfunction "VSS_10_29") (pintype "power_in"))
      (node (ref "J7") (pin "32") (pinfunction "VSS_11_32") (pintype "power_in"))
      (node (ref "J7") (pin "35") (pinfunction "VSS_12_35") (pintype "power_in"))
      (node (ref "J7") (pin "38") (pinfunction "VSS_13_38") (pintype "power_in"))
      (node (ref "J7") (pin "41") (pinfunction "VSS_14_41") (pintype "power_in"))
      (node (ref "J7") (pin "44") (pinfunction "VSS_15_44") (pintype "power_in"))
      (node (ref "J7") (pin "47") (pinfunction "VSS_16_47") (pintype "power_in"))
      (node (ref "J7") (pin "5") (pinfunction "VSS_2_5") (pintype "power_in"))
      (node (ref "J7") (pin "50") (pinfunction "VSS_17_50") (pintype "power_in"))
      (node (ref "J7") (pin "65") (pinfunction "VSS_18_65") (pintype "power_in"))
      (node (ref "J7") (pin "66") (pinfunction "VSS_19_66") (pintype "power_in"))
      (node (ref "J7") (pin "79") (pinfunction "VSS_20_79") (pintype "power_in"))
      (node (ref "J7") (pin "8") (pinfunction "VSS_3_8") (pintype "power_in"))
      (node (ref "J7") (pin "82") (pinfunction "VSS_21_82") (pintype "power_in"))
      (node (ref "J7") (pin "85") (pinfunction "VSS_22_85") (pintype "power_in"))
      (node (ref "J7") (pin "88") (pinfunction "VSS_23_88") (pintype "power_in"))
      (node (ref "J7") (pin "91") (pinfunction "VSS_24_91") (pintype "power_in"))
      (node (ref "J7") (pin "94") (pinfunction "VSS_25_94") (pintype "power_in"))
      (node (ref "J7") (pin "97") (pinfunction "VSS_26_97") (pintype "power_in"))
      (node (ref "R142") (pin "2") (pinfunction "2_2") (pintype "passive"))
      (node (ref "R143") (pin "2") (pinfunction "2_2") (pintype "passive"))
      (node (ref "U38") (pin "10") (pinfunction "GND1_10") (pintype "input"))
      (node (ref "U38") (pin "41") (pinfunction "GND2_41") (pintype "input"))
      (node (ref "U38") (pin "7") (pinfunction "AGND_7") (pintype "input"))
      (node (ref "U39") (pin "11") (pinfunction "PPAD_11") (pintype "passive"))
      (node (ref "U39") (pin "4") (pinfunction "PGND_4") (pintype "passive"))
      (node (ref "U39") (pin "8") (pinfunction "GND_8") (pintype "passive"))
    )
    (net (code "135") (name "Net-(U38-AVDD)") (class "Default")
      (node (ref "C193") (pin "1") (pinfunction "1_1") (pintype "passive"))
      (node (ref "C194") (pin "2") (pinfunction "2_2") (pintype "passive"))
      (node (ref "C195") (pin "2") (pinfunction "2_2") (pintype "passive"))
      (node (ref "L19") (pin "2") (pinfunction "2_2") (pintype "passive"))
      (node (ref "U38") (pin "8") (pinfunction "AVDD_8") (pintype "input"))
    )
    (net (code "136") (name "Net-(U38-FBIN#)") (class "Default")
      (node (ref "U38") (pin "25") (pinfunction "FBOUT#_25") (pintype "output"))
      (node (ref "U38") (pin "26") (pinfunction "FBIN#_26") (pintype "input"))
    )
    (net (code "137") (name "Net-(U38-FBIN)") (class "Default")
      (node (ref "U38") (pin "24") (pinfunction "FBOUT_24") (pintype "output"))
      (node (ref "U38") (pin "27") (pinfunction "FBIN_27") (pintype "input"))
    )
    (net (code "138") (name "Net-(U38-OE)") (class "Default")
      (node (ref "R144") (pin "2") (pinfunction "2_2") (pintype "passive"))
      (node (ref "U38") (pin "22") (pinfunction "OE_22") (pintype "input"))
    )
    (net (code "139") (name "Net-(U39-S3)") (class "Default")
      (node (ref "R146") (pin "2") (pinfunction "2_2") (pintype "passive"))
      (node (ref "U39") (pin "7") (pinfunction "S3_7") (pintype "input"))
    )
    (net (code "140") (name "Net-(U39-S5)") (class "Default")
      (node (ref "R148") (pin "1") (pinfunction "1_1") (pintype "passive"))
      (node (ref "U39") (pin "9") (pinfunction "S5_9") (pintype "input"))
    )
    (net (code "141") (name "Net-(U39-VTTSNS)") (class "Default")
      (node (ref "C178") (pin "2") (pinfunction "2_2") (pintype "passive"))
      (node (ref "R147") (pin "2") (pinfunction "2_2") (pintype "passive"))
      (node (ref "U39") (pin "5") (pinfunction "VTTSNS_5") (pintype "input"))
    )
    (net (code "142") (name "unconnected-(J7B-PAR_IN-Pad68)") (class "Default")
      (node (ref "J7") (pin "68") (pinfunction "PAR_IN_68") (pintype "input+no_connect"))
    )
    (net (code "143") (name "unconnected-(J7B-PAR_OUT-Pad55)") (class "Default")
      (node (ref "J7") (pin "55") (pinfunction "PAR_OUT_55") (pintype "output+no_connect"))
    )
    (net (code "144") (name "unconnected-(J7C-DDR2_DIMM_DQS_CB_N-Pad45)") (class "Default")
      (node (ref "J7") (pin "45") (pinfunction "DDR2_DIMM_DQS_CB_N_45") (pintype "bidirectional+no_connect"))
    )
    (net (code "145") (name "unconnected-(J7C-DDR2_DIMM_DQS_N[4]-Pad83)") (class "Default")
      (node (ref "J7") (pin "83") (pinfunction "DDR2_DIMM_DQS_N[4]_83") (pintype "bidirectional+no_connect"))
    )
    (net (code "146") (name "unconnected-(J7C-DDR2_DIMM_DQS_N[5]-Pad92)") (class "Default")
      (node (ref "J7") (pin "92") (pinfunction "DDR2_DIMM_DQS_N[5]_92") (pintype "bidirectional+no_connect"))
    )
    (net (code "147") (name "unconnected-(J7C-DDR2_DIMM_DQS_N[6]-Pad104)") (class "Default")
      (node (ref "J7") (pin "104") (pinfunction "DDR2_DIMM_DQS_N[6]_104") (pintype "bidirectional+no_connect"))
    )
    (net (code "148") (name "unconnected-(J7C-DDR2_DIMM_DQS_N[7]-Pad113)") (class "Default")
      (node (ref "J7") (pin "113") (pinfunction "DDR2_DIMM_DQS_N[7]_113") (pintype "bidirectional+no_connect"))
    )
    (net (code "149") (name "unconnected-(J7D-DDR2_DIMM_DQS_N[0]-Pad6)") (class "Default")
      (node (ref "J7") (pin "6") (pinfunction "DDR2_DIMM_DQS_N[0]_6") (pintype "bidirectional+no_connect"))
    )
    (net (code "150") (name "unconnected-(J7D-DDR2_DIMM_DQS_N[1]-Pad15)") (class "Default")
      (node (ref "J7") (pin "15") (pinfunction "DDR2_DIMM_DQS_N[1]_15") (pintype "bidirectional+no_connect"))
    )
    (net (code "151") (name "unconnected-(J7D-DDR2_DIMM_DQS_N[2]-Pad27)") (class "Default")
      (node (ref "J7") (pin "27") (pinfunction "DDR2_DIMM_DQS_N[2]_27") (pintype "bidirectional+no_connect"))
    )
    (net (code "152") (name "unconnected-(J7D-DDR2_DIMM_DQS_N[3]-Pad36)") (class "Default")
      (node (ref "J7") (pin "36") (pinfunction "DDR2_DIMM_DQS_N[3]_36") (pintype "bidirectional+no_connect"))
    )
    (net (code "153") (name "unconnected-(RP2-Pad4)") (class "Default")
      (node (ref "RP2") (pin "4") (pinfunction "4_4") (pintype "passive+no_connect"))
    )
    (net (code "154") (name "unconnected-(U38-Y0#-Pad37)") (class "Default")
      (node (ref "U38") (pin "37") (pinfunction "Y0#_37") (pintype "output+no_connect"))
    )
    (net (code "155") (name "unconnected-(U38-Y0-Pad38)") (class "Default")
      (node (ref "U38") (pin "38") (pinfunction "Y0_38") (pintype "output+no_connect"))
    )
    (net (code "156") (name "unconnected-(U38-Y2#-Pad2)") (class "Default")
      (node (ref "U38") (pin "2") (pinfunction "Y2#_2") (pintype "output+no_connect"))
    )
    (net (code "157") (name "unconnected-(U38-Y2-Pad3)") (class "Default")
      (node (ref "U38") (pin "3") (pinfunction "Y2_3") (pintype "output+no_connect"))
    )
    (net (code "158") (name "unconnected-(U38-Y3#-Pad12)") (class "Default")
      (node (ref "U38") (pin "12") (pinfunction "Y3#_12") (pintype "output+no_connect"))
    )
    (net (code "159") (name "unconnected-(U38-Y3-Pad11)") (class "Default")
      (node (ref "U38") (pin "11") (pinfunction "Y3_11") (pintype "output+no_connect"))
    )
    (net (code "160") (name "unconnected-(U38-Y4#-Pad13)") (class "Default")
      (node (ref "U38") (pin "13") (pinfunction "Y4#_13") (pintype "output+no_connect"))
    )
    (net (code "161") (name "unconnected-(U38-Y4-Pad14)") (class "Default")
      (node (ref "U38") (pin "14") (pinfunction "Y4_14") (pintype "output+no_connect"))
    )
    (net (code "162") (name "unconnected-(U38-Y5#-Pad35)") (class "Default")
      (node (ref "U38") (pin "35") (pinfunction "Y5#_35") (pintype "output+no_connect"))
    )
    (net (code "163") (name "unconnected-(U38-Y5-Pad34)") (class "Default")
      (node (ref "U38") (pin "34") (pinfunction "Y5_34") (pintype "output+no_connect"))
    )
    (net (code "164") (name "unconnected-(U38-Y6#-Pad32)") (class "Default")
      (node (ref "U38") (pin "32") (pinfunction "Y6#_32") (pintype "output+no_connect"))
    )
    (net (code "165") (name "unconnected-(U38-Y6-Pad33)") (class "Default")
      (node (ref "U38") (pin "33") (pinfunction "Y6_33") (pintype "output+no_connect"))
    )
    (net (code "166") (name "unconnected-(U38-Y7#-Pad30)") (class "Default")
      (node (ref "U38") (pin "30") (pinfunction "Y7#_30") (pintype "output+no_connect"))
    )
    (net (code "167") (name "unconnected-(U38-Y7-Pad29)") (class "Default")
      (node (ref "U38") (pin "29") (pinfunction "Y7_29") (pintype "output+no_connect"))
    )
  )
)
